# SmartLEDS.net
KiCad netlist of a schematic drawn in Altium Designer
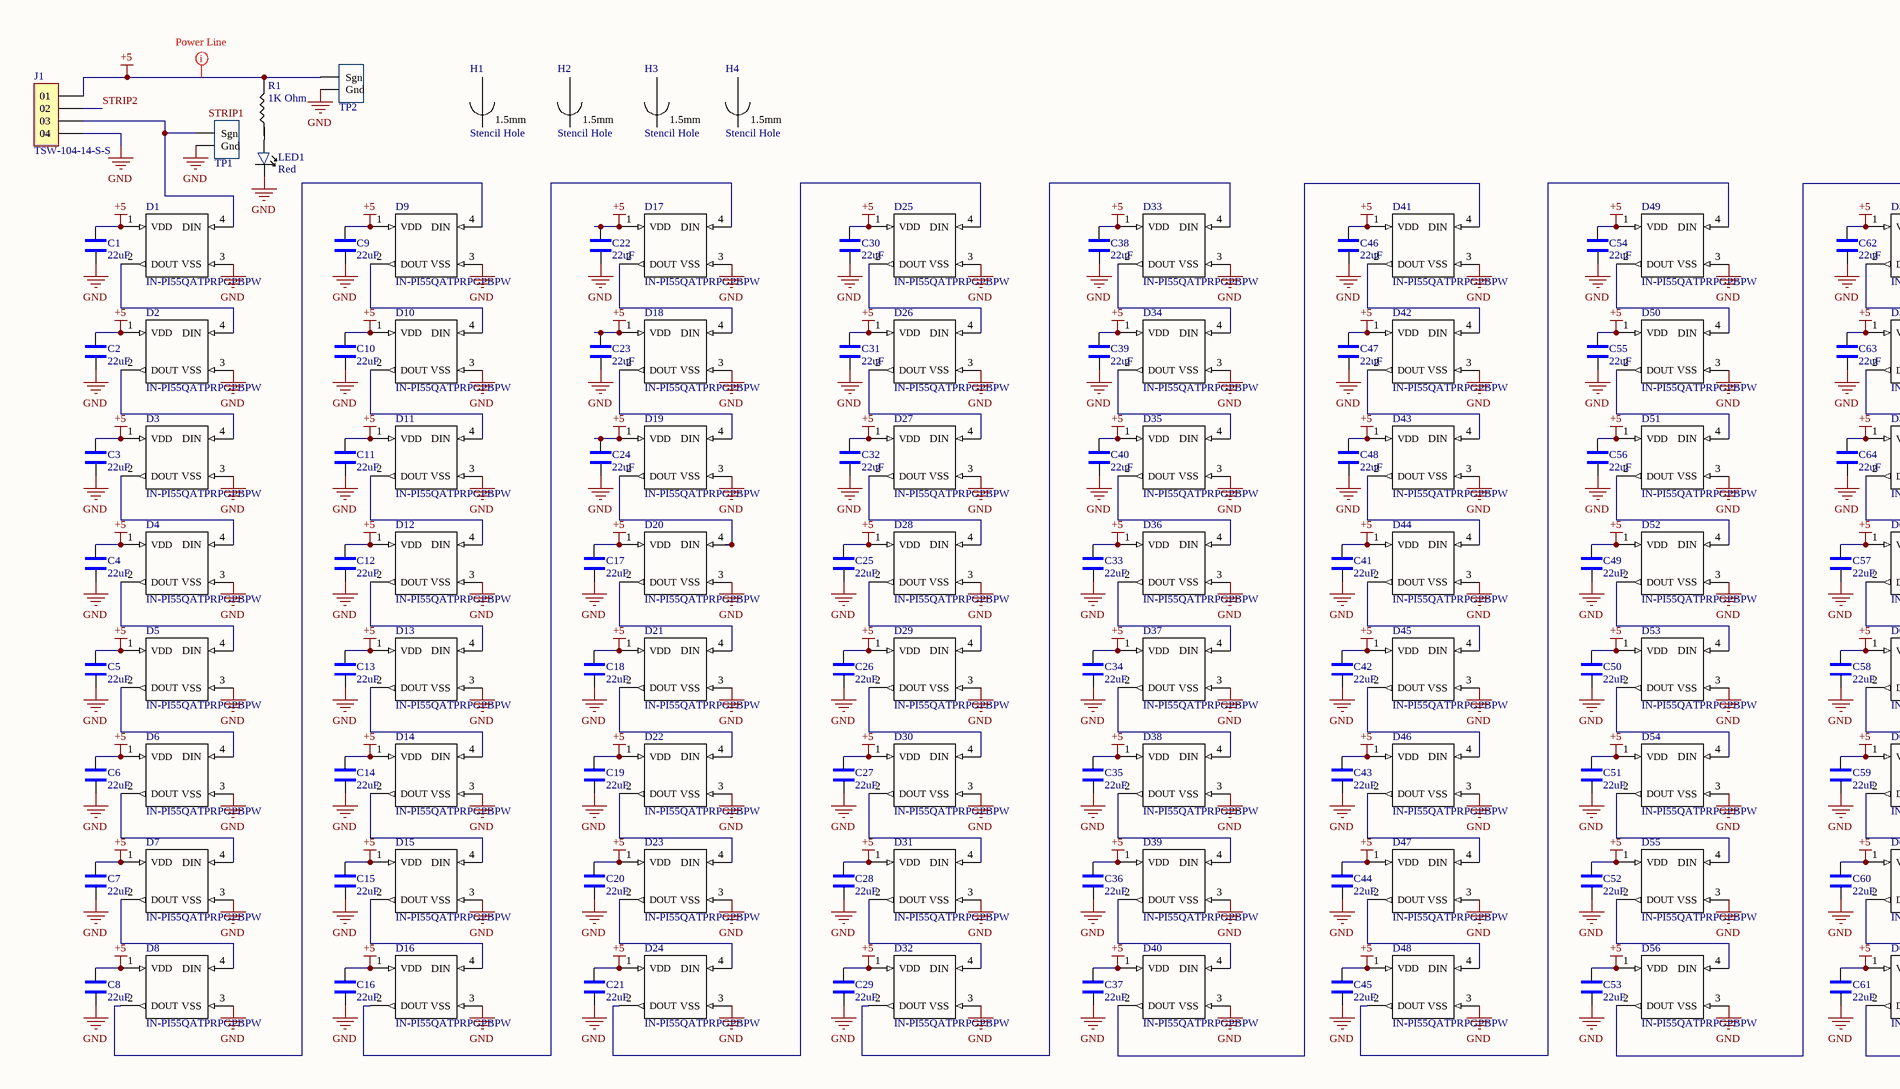
[diagram p0: SmartLEDS.SchDoc, left]
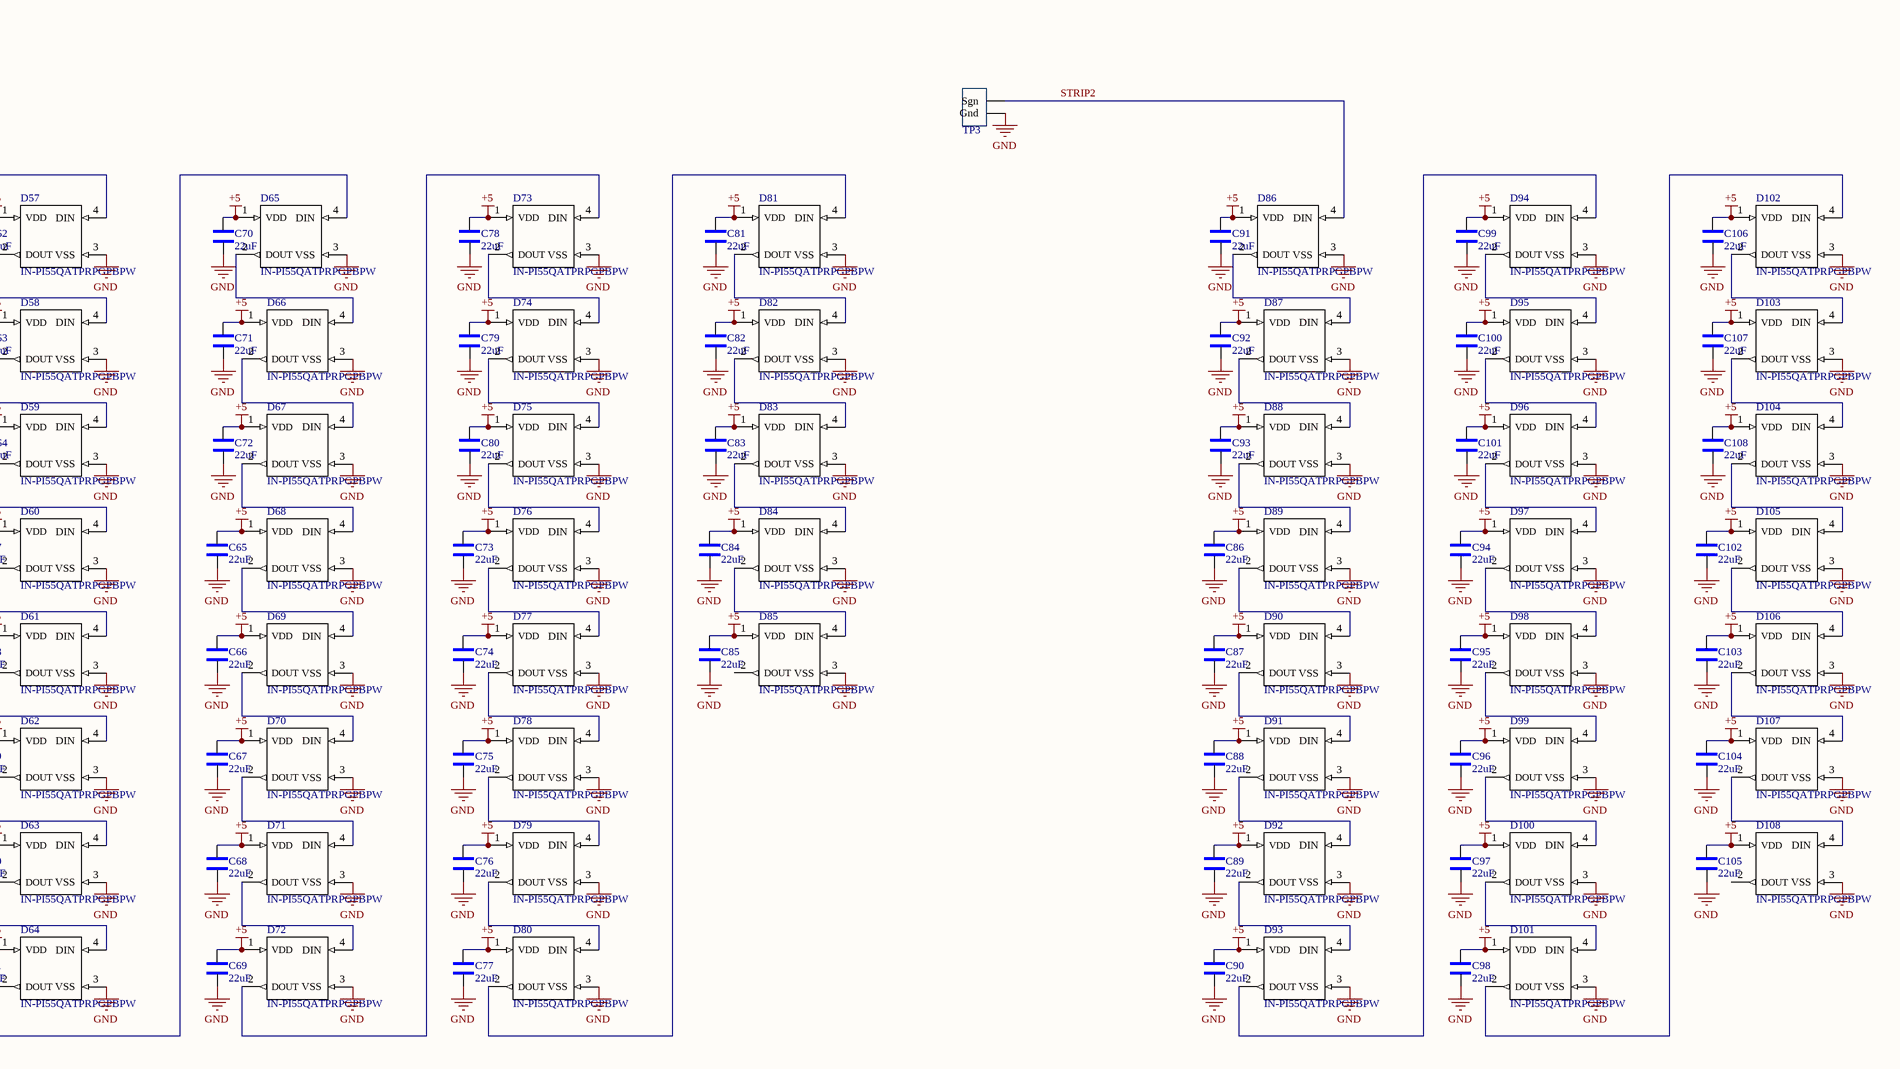
[diagram p1: SmartLEDS.SchDoc, right]

(export (version "E")
  (design (tool "Eeschema 10.0.6"))
  (components
    (comp (ref "C1")
      (value "22uF")
      (footprint "1206_Passive_Capacitor")
      (description "22uF ±10% 25V X5R 1206 Multilayer Ceramic Capacitors MLCC - SMD/SMT RoHS")
      (fields (field (name "MFR PART #") "CL31A226KAHNNNE") (field (name "LCSC PART#") "C12891"))
      (libsource (lib "ECEN5730Lib_2023_05_DS") (part "C_22uF_1206"))
    )
    (comp (ref "C2")
      (value "22uF")
      (footprint "1206_Passive_Capacitor")
      (description "22uF ±10% 25V X5R 1206 Multilayer Ceramic Capacitors MLCC - SMD/SMT RoHS")
      (fields (field (name "MFR PART #") "CL31A226KAHNNNE") (field (name "LCSC PART#") "C12891"))
      (libsource (lib "ECEN5730Lib_2023_05_DS") (part "C_22uF_1206"))
    )
    (comp (ref "C3")
      (value "22uF")
      (footprint "1206_Passive_Capacitor")
      (description "22uF ±10% 25V X5R 1206 Multilayer Ceramic Capacitors MLCC - SMD/SMT RoHS")
      (fields (field (name "MFR PART #") "CL31A226KAHNNNE") (field (name "LCSC PART#") "C12891"))
      (libsource (lib "ECEN5730Lib_2023_05_DS") (part "C_22uF_1206"))
    )
    (comp (ref "C4")
      (value "22uF")
      (footprint "1206_Passive_Capacitor")
      (description "22uF ±10% 25V X5R 1206 Multilayer Ceramic Capacitors MLCC - SMD/SMT RoHS")
      (fields (field (name "MFR PART #") "CL31A226KAHNNNE") (field (name "LCSC PART#") "C12891"))
      (libsource (lib "ECEN5730Lib_2023_05_DS") (part "C_22uF_1206"))
    )
    (comp (ref "C5")
      (value "22uF")
      (footprint "1206_Passive_Capacitor")
      (description "22uF ±10% 25V X5R 1206 Multilayer Ceramic Capacitors MLCC - SMD/SMT RoHS")
      (fields (field (name "MFR PART #") "CL31A226KAHNNNE") (field (name "LCSC PART#") "C12891"))
      (libsource (lib "ECEN5730Lib_2023_05_DS") (part "C_22uF_1206"))
    )
    (comp (ref "C6")
      (value "22uF")
      (footprint "1206_Passive_Capacitor")
      (description "22uF ±10% 25V X5R 1206 Multilayer Ceramic Capacitors MLCC - SMD/SMT RoHS")
      (fields (field (name "MFR PART #") "CL31A226KAHNNNE") (field (name "LCSC PART#") "C12891"))
      (libsource (lib "ECEN5730Lib_2023_05_DS") (part "C_22uF_1206"))
    )
    (comp (ref "C7")
      (value "22uF")
      (footprint "1206_Passive_Capacitor")
      (description "22uF ±10% 25V X5R 1206 Multilayer Ceramic Capacitors MLCC - SMD/SMT RoHS")
      (fields (field (name "MFR PART #") "CL31A226KAHNNNE") (field (name "LCSC PART#") "C12891"))
      (libsource (lib "ECEN5730Lib_2023_05_DS") (part "C_22uF_1206"))
    )
    (comp (ref "C8")
      (value "22uF")
      (footprint "1206_Passive_Capacitor")
      (description "22uF ±10% 25V X5R 1206 Multilayer Ceramic Capacitors MLCC - SMD/SMT RoHS")
      (fields (field (name "MFR PART #") "CL31A226KAHNNNE") (field (name "LCSC PART#") "C12891"))
      (libsource (lib "ECEN5730Lib_2023_05_DS") (part "C_22uF_1206"))
    )
    (comp (ref "C9")
      (value "22uF")
      (footprint "1206_Passive_Capacitor")
      (description "22uF ±10% 25V X5R 1206 Multilayer Ceramic Capacitors MLCC - SMD/SMT RoHS")
      (fields (field (name "MFR PART #") "CL31A226KAHNNNE") (field (name "LCSC PART#") "C12891"))
      (libsource (lib "ECEN5730Lib_2023_05_DS") (part "C_22uF_1206"))
    )
    (comp (ref "C10")
      (value "22uF")
      (footprint "1206_Passive_Capacitor")
      (description "22uF ±10% 25V X5R 1206 Multilayer Ceramic Capacitors MLCC - SMD/SMT RoHS")
      (fields (field (name "MFR PART #") "CL31A226KAHNNNE") (field (name "LCSC PART#") "C12891"))
      (libsource (lib "ECEN5730Lib_2023_05_DS") (part "C_22uF_1206"))
    )
    (comp (ref "C11")
      (value "22uF")
      (footprint "1206_Passive_Capacitor")
      (description "22uF ±10% 25V X5R 1206 Multilayer Ceramic Capacitors MLCC - SMD/SMT RoHS")
      (fields (field (name "MFR PART #") "CL31A226KAHNNNE") (field (name "LCSC PART#") "C12891"))
      (libsource (lib "ECEN5730Lib_2023_05_DS") (part "C_22uF_1206"))
    )
    (comp (ref "C12")
      (value "22uF")
      (footprint "1206_Passive_Capacitor")
      (description "22uF ±10% 25V X5R 1206 Multilayer Ceramic Capacitors MLCC - SMD/SMT RoHS")
      (fields (field (name "MFR PART #") "CL31A226KAHNNNE") (field (name "LCSC PART#") "C12891"))
      (libsource (lib "ECEN5730Lib_2023_05_DS") (part "C_22uF_1206"))
    )
    (comp (ref "C13")
      (value "22uF")
      (footprint "1206_Passive_Capacitor")
      (description "22uF ±10% 25V X5R 1206 Multilayer Ceramic Capacitors MLCC - SMD/SMT RoHS")
      (fields (field (name "MFR PART #") "CL31A226KAHNNNE") (field (name "LCSC PART#") "C12891"))
      (libsource (lib "ECEN5730Lib_2023_05_DS") (part "C_22uF_1206"))
    )
    (comp (ref "C14")
      (value "22uF")
      (footprint "1206_Passive_Capacitor")
      (description "22uF ±10% 25V X5R 1206 Multilayer Ceramic Capacitors MLCC - SMD/SMT RoHS")
      (fields (field (name "MFR PART #") "CL31A226KAHNNNE") (field (name "LCSC PART#") "C12891"))
      (libsource (lib "ECEN5730Lib_2023_05_DS") (part "C_22uF_1206"))
    )
    (comp (ref "C15")
      (value "22uF")
      (footprint "1206_Passive_Capacitor")
      (description "22uF ±10% 25V X5R 1206 Multilayer Ceramic Capacitors MLCC - SMD/SMT RoHS")
      (fields (field (name "MFR PART #") "CL31A226KAHNNNE") (field (name "LCSC PART#") "C12891"))
      (libsource (lib "ECEN5730Lib_2023_05_DS") (part "C_22uF_1206"))
    )
    (comp (ref "C16")
      (value "22uF")
      (footprint "1206_Passive_Capacitor")
      (description "22uF ±10% 25V X5R 1206 Multilayer Ceramic Capacitors MLCC - SMD/SMT RoHS")
      (fields (field (name "MFR PART #") "CL31A226KAHNNNE") (field (name "LCSC PART#") "C12891"))
      (libsource (lib "ECEN5730Lib_2023_05_DS") (part "C_22uF_1206"))
    )
    (comp (ref "C17")
      (value "22uF")
      (footprint "1206_Passive_Capacitor")
      (description "22uF ±10% 25V X5R 1206 Multilayer Ceramic Capacitors MLCC - SMD/SMT RoHS")
      (fields (field (name "MFR PART #") "CL31A226KAHNNNE") (field (name "LCSC PART#") "C12891"))
      (libsource (lib "ECEN5730Lib_2023_05_DS") (part "C_22uF_1206"))
    )
    (comp (ref "C18")
      (value "22uF")
      (footprint "1206_Passive_Capacitor")
      (description "22uF ±10% 25V X5R 1206 Multilayer Ceramic Capacitors MLCC - SMD/SMT RoHS")
      (fields (field (name "MFR PART #") "CL31A226KAHNNNE") (field (name "LCSC PART#") "C12891"))
      (libsource (lib "ECEN5730Lib_2023_05_DS") (part "C_22uF_1206"))
    )
    (comp (ref "C19")
      (value "22uF")
      (footprint "1206_Passive_Capacitor")
      (description "22uF ±10% 25V X5R 1206 Multilayer Ceramic Capacitors MLCC - SMD/SMT RoHS")
      (fields (field (name "MFR PART #") "CL31A226KAHNNNE") (field (name "LCSC PART#") "C12891"))
      (libsource (lib "ECEN5730Lib_2023_05_DS") (part "C_22uF_1206"))
    )
    (comp (ref "C20")
      (value "22uF")
      (footprint "1206_Passive_Capacitor")
      (description "22uF ±10% 25V X5R 1206 Multilayer Ceramic Capacitors MLCC - SMD/SMT RoHS")
      (fields (field (name "MFR PART #") "CL31A226KAHNNNE") (field (name "LCSC PART#") "C12891"))
      (libsource (lib "ECEN5730Lib_2023_05_DS") (part "C_22uF_1206"))
    )
    (comp (ref "C21")
      (value "22uF")
      (footprint "1206_Passive_Capacitor")
      (description "22uF ±10% 25V X5R 1206 Multilayer Ceramic Capacitors MLCC - SMD/SMT RoHS")
      (fields (field (name "MFR PART #") "CL31A226KAHNNNE") (field (name "LCSC PART#") "C12891"))
      (libsource (lib "ECEN5730Lib_2023_05_DS") (part "C_22uF_1206"))
    )
    (comp (ref "C22")
      (value "22uF")
      (footprint "1206_Passive_Capacitor")
      (description "22uF ±10% 25V X5R 1206 Multilayer Ceramic Capacitors MLCC - SMD/SMT RoHS")
      (fields (field (name "MFR PART #") "CL31A226KAHNNNE") (field (name "LCSC PART#") "C12891"))
      (libsource (lib "ECEN5730Lib_2023_05_DS") (part "C_22uF_1206"))
    )
    (comp (ref "C23")
      (value "22uF")
      (footprint "1206_Passive_Capacitor")
      (description "22uF ±10% 25V X5R 1206 Multilayer Ceramic Capacitors MLCC - SMD/SMT RoHS")
      (fields (field (name "MFR PART #") "CL31A226KAHNNNE") (field (name "LCSC PART#") "C12891"))
      (libsource (lib "ECEN5730Lib_2023_05_DS") (part "C_22uF_1206"))
    )
    (comp (ref "C24")
      (value "22uF")
      (footprint "1206_Passive_Capacitor")
      (description "22uF ±10% 25V X5R 1206 Multilayer Ceramic Capacitors MLCC - SMD/SMT RoHS")
      (fields (field (name "MFR PART #") "CL31A226KAHNNNE") (field (name "LCSC PART#") "C12891"))
      (libsource (lib "ECEN5730Lib_2023_05_DS") (part "C_22uF_1206"))
    )
    (comp (ref "C25")
      (value "22uF")
      (footprint "1206_Passive_Capacitor")
      (description "22uF ±10% 25V X5R 1206 Multilayer Ceramic Capacitors MLCC - SMD/SMT RoHS")
      (fields (field (name "MFR PART #") "CL31A226KAHNNNE") (field (name "LCSC PART#") "C12891"))
      (libsource (lib "ECEN5730Lib_2023_05_DS") (part "C_22uF_1206"))
    )
    (comp (ref "C26")
      (value "22uF")
      (footprint "1206_Passive_Capacitor")
      (description "22uF ±10% 25V X5R 1206 Multilayer Ceramic Capacitors MLCC - SMD/SMT RoHS")
      (fields (field (name "MFR PART #") "CL31A226KAHNNNE") (field (name "LCSC PART#") "C12891"))
      (libsource (lib "ECEN5730Lib_2023_05_DS") (part "C_22uF_1206"))
    )
    (comp (ref "C27")
      (value "22uF")
      (footprint "1206_Passive_Capacitor")
      (description "22uF ±10% 25V X5R 1206 Multilayer Ceramic Capacitors MLCC - SMD/SMT RoHS")
      (fields (field (name "MFR PART #") "CL31A226KAHNNNE") (field (name "LCSC PART#") "C12891"))
      (libsource (lib "ECEN5730Lib_2023_05_DS") (part "C_22uF_1206"))
    )
    (comp (ref "C28")
      (value "22uF")
      (footprint "1206_Passive_Capacitor")
      (description "22uF ±10% 25V X5R 1206 Multilayer Ceramic Capacitors MLCC - SMD/SMT RoHS")
      (fields (field (name "MFR PART #") "CL31A226KAHNNNE") (field (name "LCSC PART#") "C12891"))
      (libsource (lib "ECEN5730Lib_2023_05_DS") (part "C_22uF_1206"))
    )
    (comp (ref "C29")
      (value "22uF")
      (footprint "1206_Passive_Capacitor")
      (description "22uF ±10% 25V X5R 1206 Multilayer Ceramic Capacitors MLCC - SMD/SMT RoHS")
      (fields (field (name "MFR PART #") "CL31A226KAHNNNE") (field (name "LCSC PART#") "C12891"))
      (libsource (lib "ECEN5730Lib_2023_05_DS") (part "C_22uF_1206"))
    )
    (comp (ref "C30")
      (value "22uF")
      (footprint "1206_Passive_Capacitor")
      (description "22uF ±10% 25V X5R 1206 Multilayer Ceramic Capacitors MLCC - SMD/SMT RoHS")
      (fields (field (name "MFR PART #") "CL31A226KAHNNNE") (field (name "LCSC PART#") "C12891"))
      (libsource (lib "ECEN5730Lib_2023_05_DS") (part "C_22uF_1206"))
    )
    (comp (ref "C31")
      (value "22uF")
      (footprint "1206_Passive_Capacitor")
      (description "22uF ±10% 25V X5R 1206 Multilayer Ceramic Capacitors MLCC - SMD/SMT RoHS")
      (fields (field (name "MFR PART #") "CL31A226KAHNNNE") (field (name "LCSC PART#") "C12891"))
      (libsource (lib "ECEN5730Lib_2023_05_DS") (part "C_22uF_1206"))
    )
    (comp (ref "C32")
      (value "22uF")
      (footprint "1206_Passive_Capacitor")
      (description "22uF ±10% 25V X5R 1206 Multilayer Ceramic Capacitors MLCC - SMD/SMT RoHS")
      (fields (field (name "MFR PART #") "CL31A226KAHNNNE") (field (name "LCSC PART#") "C12891"))
      (libsource (lib "ECEN5730Lib_2023_05_DS") (part "C_22uF_1206"))
    )
    (comp (ref "C33")
      (value "22uF")
      (footprint "1206_Passive_Capacitor")
      (description "22uF ±10% 25V X5R 1206 Multilayer Ceramic Capacitors MLCC - SMD/SMT RoHS")
      (fields (field (name "MFR PART #") "CL31A226KAHNNNE") (field (name "LCSC PART#") "C12891"))
      (libsource (lib "ECEN5730Lib_2023_05_DS") (part "C_22uF_1206"))
    )
    (comp (ref "C34")
      (value "22uF")
      (footprint "1206_Passive_Capacitor")
      (description "22uF ±10% 25V X5R 1206 Multilayer Ceramic Capacitors MLCC - SMD/SMT RoHS")
      (fields (field (name "MFR PART #") "CL31A226KAHNNNE") (field (name "LCSC PART#") "C12891"))
      (libsource (lib "ECEN5730Lib_2023_05_DS") (part "C_22uF_1206"))
    )
    (comp (ref "C35")
      (value "22uF")
      (footprint "1206_Passive_Capacitor")
      (description "22uF ±10% 25V X5R 1206 Multilayer Ceramic Capacitors MLCC - SMD/SMT RoHS")
      (fields (field (name "MFR PART #") "CL31A226KAHNNNE") (field (name "LCSC PART#") "C12891"))
      (libsource (lib "ECEN5730Lib_2023_05_DS") (part "C_22uF_1206"))
    )
    (comp (ref "C36")
      (value "22uF")
      (footprint "1206_Passive_Capacitor")
      (description "22uF ±10% 25V X5R 1206 Multilayer Ceramic Capacitors MLCC - SMD/SMT RoHS")
      (fields (field (name "MFR PART #") "CL31A226KAHNNNE") (field (name "LCSC PART#") "C12891"))
      (libsource (lib "ECEN5730Lib_2023_05_DS") (part "C_22uF_1206"))
    )
    (comp (ref "C37")
      (value "22uF")
      (footprint "1206_Passive_Capacitor")
      (description "22uF ±10% 25V X5R 1206 Multilayer Ceramic Capacitors MLCC - SMD/SMT RoHS")
      (fields (field (name "MFR PART #") "CL31A226KAHNNNE") (field (name "LCSC PART#") "C12891"))
      (libsource (lib "ECEN5730Lib_2023_05_DS") (part "C_22uF_1206"))
    )
    (comp (ref "C38")
      (value "22uF")
      (footprint "1206_Passive_Capacitor")
      (description "22uF ±10% 25V X5R 1206 Multilayer Ceramic Capacitors MLCC - SMD/SMT RoHS")
      (fields (field (name "MFR PART #") "CL31A226KAHNNNE") (field (name "LCSC PART#") "C12891"))
      (libsource (lib "ECEN5730Lib_2023_05_DS") (part "C_22uF_1206"))
    )
    (comp (ref "C39")
      (value "22uF")
      (footprint "1206_Passive_Capacitor")
      (description "22uF ±10% 25V X5R 1206 Multilayer Ceramic Capacitors MLCC - SMD/SMT RoHS")
      (fields (field (name "MFR PART #") "CL31A226KAHNNNE") (field (name "LCSC PART#") "C12891"))
      (libsource (lib "ECEN5730Lib_2023_05_DS") (part "C_22uF_1206"))
    )
    (comp (ref "C40")
      (value "22uF")
      (footprint "1206_Passive_Capacitor")
      (description "22uF ±10% 25V X5R 1206 Multilayer Ceramic Capacitors MLCC - SMD/SMT RoHS")
      (fields (field (name "MFR PART #") "CL31A226KAHNNNE") (field (name "LCSC PART#") "C12891"))
      (libsource (lib "ECEN5730Lib_2023_05_DS") (part "C_22uF_1206"))
    )
    (comp (ref "C41")
      (value "22uF")
      (footprint "1206_Passive_Capacitor")
      (description "22uF ±10% 25V X5R 1206 Multilayer Ceramic Capacitors MLCC - SMD/SMT RoHS")
      (fields (field (name "MFR PART #") "CL31A226KAHNNNE") (field (name "LCSC PART#") "C12891"))
      (libsource (lib "ECEN5730Lib_2023_05_DS") (part "C_22uF_1206"))
    )
    (comp (ref "C42")
      (value "22uF")
      (footprint "1206_Passive_Capacitor")
      (description "22uF ±10% 25V X5R 1206 Multilayer Ceramic Capacitors MLCC - SMD/SMT RoHS")
      (fields (field (name "MFR PART #") "CL31A226KAHNNNE") (field (name "LCSC PART#") "C12891"))
      (libsource (lib "ECEN5730Lib_2023_05_DS") (part "C_22uF_1206"))
    )
    (comp (ref "C43")
      (value "22uF")
      (footprint "1206_Passive_Capacitor")
      (description "22uF ±10% 25V X5R 1206 Multilayer Ceramic Capacitors MLCC - SMD/SMT RoHS")
      (fields (field (name "MFR PART #") "CL31A226KAHNNNE") (field (name "LCSC PART#") "C12891"))
      (libsource (lib "ECEN5730Lib_2023_05_DS") (part "C_22uF_1206"))
    )
    (comp (ref "C44")
      (value "22uF")
      (footprint "1206_Passive_Capacitor")
      (description "22uF ±10% 25V X5R 1206 Multilayer Ceramic Capacitors MLCC - SMD/SMT RoHS")
      (fields (field (name "MFR PART #") "CL31A226KAHNNNE") (field (name "LCSC PART#") "C12891"))
      (libsource (lib "ECEN5730Lib_2023_05_DS") (part "C_22uF_1206"))
    )
    (comp (ref "C45")
      (value "22uF")
      (footprint "1206_Passive_Capacitor")
      (description "22uF ±10% 25V X5R 1206 Multilayer Ceramic Capacitors MLCC - SMD/SMT RoHS")
      (fields (field (name "MFR PART #") "CL31A226KAHNNNE") (field (name "LCSC PART#") "C12891"))
      (libsource (lib "ECEN5730Lib_2023_05_DS") (part "C_22uF_1206"))
    )
    (comp (ref "C46")
      (value "22uF")
      (footprint "1206_Passive_Capacitor")
      (description "22uF ±10% 25V X5R 1206 Multilayer Ceramic Capacitors MLCC - SMD/SMT RoHS")
      (fields (field (name "MFR PART #") "CL31A226KAHNNNE") (field (name "LCSC PART#") "C12891"))
      (libsource (lib "ECEN5730Lib_2023_05_DS") (part "C_22uF_1206"))
    )
    (comp (ref "C47")
      (value "22uF")
      (footprint "1206_Passive_Capacitor")
      (description "22uF ±10% 25V X5R 1206 Multilayer Ceramic Capacitors MLCC - SMD/SMT RoHS")
      (fields (field (name "MFR PART #") "CL31A226KAHNNNE") (field (name "LCSC PART#") "C12891"))
      (libsource (lib "ECEN5730Lib_2023_05_DS") (part "C_22uF_1206"))
    )
    (comp (ref "C48")
      (value "22uF")
      (footprint "1206_Passive_Capacitor")
      (description "22uF ±10% 25V X5R 1206 Multilayer Ceramic Capacitors MLCC - SMD/SMT RoHS")
      (fields (field (name "MFR PART #") "CL31A226KAHNNNE") (field (name "LCSC PART#") "C12891"))
      (libsource (lib "ECEN5730Lib_2023_05_DS") (part "C_22uF_1206"))
    )
    (comp (ref "C49")
      (value "22uF")
      (footprint "1206_Passive_Capacitor")
      (description "22uF ±10% 25V X5R 1206 Multilayer Ceramic Capacitors MLCC - SMD/SMT RoHS")
      (fields (field (name "MFR PART #") "CL31A226KAHNNNE") (field (name "LCSC PART#") "C12891"))
      (libsource (lib "ECEN5730Lib_2023_05_DS") (part "C_22uF_1206"))
    )
    (comp (ref "C50")
      (value "22uF")
      (footprint "1206_Passive_Capacitor")
      (description "22uF ±10% 25V X5R 1206 Multilayer Ceramic Capacitors MLCC - SMD/SMT RoHS")
      (fields (field (name "MFR PART #") "CL31A226KAHNNNE") (field (name "LCSC PART#") "C12891"))
      (libsource (lib "ECEN5730Lib_2023_05_DS") (part "C_22uF_1206"))
    )
    (comp (ref "C51")
      (value "22uF")
      (footprint "1206_Passive_Capacitor")
      (description "22uF ±10% 25V X5R 1206 Multilayer Ceramic Capacitors MLCC - SMD/SMT RoHS")
      (fields (field (name "MFR PART #") "CL31A226KAHNNNE") (field (name "LCSC PART#") "C12891"))
      (libsource (lib "ECEN5730Lib_2023_05_DS") (part "C_22uF_1206"))
    )
    (comp (ref "C52")
      (value "22uF")
      (footprint "1206_Passive_Capacitor")
      (description "22uF ±10% 25V X5R 1206 Multilayer Ceramic Capacitors MLCC - SMD/SMT RoHS")
      (fields (field (name "MFR PART #") "CL31A226KAHNNNE") (field (name "LCSC PART#") "C12891"))
      (libsource (lib "ECEN5730Lib_2023_05_DS") (part "C_22uF_1206"))
    )
    (comp (ref "C53")
      (value "22uF")
      (footprint "1206_Passive_Capacitor")
      (description "22uF ±10% 25V X5R 1206 Multilayer Ceramic Capacitors MLCC - SMD/SMT RoHS")
      (fields (field (name "MFR PART #") "CL31A226KAHNNNE") (field (name "LCSC PART#") "C12891"))
      (libsource (lib "ECEN5730Lib_2023_05_DS") (part "C_22uF_1206"))
    )
    (comp (ref "C54")
      (value "22uF")
      (footprint "1206_Passive_Capacitor")
      (description "22uF ±10% 25V X5R 1206 Multilayer Ceramic Capacitors MLCC - SMD/SMT RoHS")
      (fields (field (name "MFR PART #") "CL31A226KAHNNNE") (field (name "LCSC PART#") "C12891"))
      (libsource (lib "ECEN5730Lib_2023_05_DS") (part "C_22uF_1206"))
    )
    (comp (ref "C55")
      (value "22uF")
      (footprint "1206_Passive_Capacitor")
      (description "22uF ±10% 25V X5R 1206 Multilayer Ceramic Capacitors MLCC - SMD/SMT RoHS")
      (fields (field (name "MFR PART #") "CL31A226KAHNNNE") (field (name "LCSC PART#") "C12891"))
      (libsource (lib "ECEN5730Lib_2023_05_DS") (part "C_22uF_1206"))
    )
    (comp (ref "C56")
      (value "22uF")
      (footprint "1206_Passive_Capacitor")
      (description "22uF ±10% 25V X5R 1206 Multilayer Ceramic Capacitors MLCC - SMD/SMT RoHS")
      (fields (field (name "MFR PART #") "CL31A226KAHNNNE") (field (name "LCSC PART#") "C12891"))
      (libsource (lib "ECEN5730Lib_2023_05_DS") (part "C_22uF_1206"))
    )
    (comp (ref "C57")
      (value "22uF")
      (footprint "1206_Passive_Capacitor")
      (description "22uF ±10% 25V X5R 1206 Multilayer Ceramic Capacitors MLCC - SMD/SMT RoHS")
      (fields (field (name "MFR PART #") "CL31A226KAHNNNE") (field (name "LCSC PART#") "C12891"))
      (libsource (lib "ECEN5730Lib_2023_05_DS") (part "C_22uF_1206"))
    )
    (comp (ref "C58")
      (value "22uF")
      (footprint "1206_Passive_Capacitor")
      (description "22uF ±10% 25V X5R 1206 Multilayer Ceramic Capacitors MLCC - SMD/SMT RoHS")
      (fields (field (name "MFR PART #") "CL31A226KAHNNNE") (field (name "LCSC PART#") "C12891"))
      (libsource (lib "ECEN5730Lib_2023_05_DS") (part "C_22uF_1206"))
    )
    (comp (ref "C59")
      (value "22uF")
      (footprint "1206_Passive_Capacitor")
      (description "22uF ±10% 25V X5R 1206 Multilayer Ceramic Capacitors MLCC - SMD/SMT RoHS")
      (fields (field (name "MFR PART #") "CL31A226KAHNNNE") (field (name "LCSC PART#") "C12891"))
      (libsource (lib "ECEN5730Lib_2023_05_DS") (part "C_22uF_1206"))
    )
    (comp (ref "C60")
      (value "22uF")
      (footprint "1206_Passive_Capacitor")
      (description "22uF ±10% 25V X5R 1206 Multilayer Ceramic Capacitors MLCC - SMD/SMT RoHS")
      (fields (field (name "MFR PART #") "CL31A226KAHNNNE") (field (name "LCSC PART#") "C12891"))
      (libsource (lib "ECEN5730Lib_2023_05_DS") (part "C_22uF_1206"))
    )
    (comp (ref "C61")
      (value "22uF")
      (footprint "1206_Passive_Capacitor")
      (description "22uF ±10% 25V X5R 1206 Multilayer Ceramic Capacitors MLCC - SMD/SMT RoHS")
      (fields (field (name "MFR PART #") "CL31A226KAHNNNE") (field (name "LCSC PART#") "C12891"))
      (libsource (lib "ECEN5730Lib_2023_05_DS") (part "C_22uF_1206"))
    )
    (comp (ref "C62")
      (value "22uF")
      (footprint "1206_Passive_Capacitor")
      (description "22uF ±10% 25V X5R 1206 Multilayer Ceramic Capacitors MLCC - SMD/SMT RoHS")
      (fields (field (name "MFR PART #") "CL31A226KAHNNNE") (field (name "LCSC PART#") "C12891"))
      (libsource (lib "ECEN5730Lib_2023_05_DS") (part "C_22uF_1206"))
    )
    (comp (ref "C63")
      (value "22uF")
      (footprint "1206_Passive_Capacitor")
      (description "22uF ±10% 25V X5R 1206 Multilayer Ceramic Capacitors MLCC - SMD/SMT RoHS")
      (fields (field (name "MFR PART #") "CL31A226KAHNNNE") (field (name "LCSC PART#") "C12891"))
      (libsource (lib "ECEN5730Lib_2023_05_DS") (part "C_22uF_1206"))
    )
    (comp (ref "C64")
      (value "22uF")
      (footprint "1206_Passive_Capacitor")
      (description "22uF ±10% 25V X5R 1206 Multilayer Ceramic Capacitors MLCC - SMD/SMT RoHS")
      (fields (field (name "MFR PART #") "CL31A226KAHNNNE") (field (name "LCSC PART#") "C12891"))
      (libsource (lib "ECEN5730Lib_2023_05_DS") (part "C_22uF_1206"))
    )
    (comp (ref "C65")
      (value "22uF")
      (footprint "1206_Passive_Capacitor")
      (description "22uF ±10% 25V X5R 1206 Multilayer Ceramic Capacitors MLCC - SMD/SMT RoHS")
      (fields (field (name "MFR PART #") "CL31A226KAHNNNE") (field (name "LCSC PART#") "C12891"))
      (libsource (lib "ECEN5730Lib_2023_05_DS") (part "C_22uF_1206"))
    )
    (comp (ref "C66")
      (value "22uF")
      (footprint "1206_Passive_Capacitor")
      (description "22uF ±10% 25V X5R 1206 Multilayer Ceramic Capacitors MLCC - SMD/SMT RoHS")
      (fields (field (name "MFR PART #") "CL31A226KAHNNNE") (field (name "LCSC PART#") "C12891"))
      (libsource (lib "ECEN5730Lib_2023_05_DS") (part "C_22uF_1206"))
    )
    (comp (ref "C67")
      (value "22uF")
      (footprint "1206_Passive_Capacitor")
      (description "22uF ±10% 25V X5R 1206 Multilayer Ceramic Capacitors MLCC - SMD/SMT RoHS")
      (fields (field (name "MFR PART #") "CL31A226KAHNNNE") (field (name "LCSC PART#") "C12891"))
      (libsource (lib "ECEN5730Lib_2023_05_DS") (part "C_22uF_1206"))
    )
    (comp (ref "C68")
      (value "22uF")
      (footprint "1206_Passive_Capacitor")
      (description "22uF ±10% 25V X5R 1206 Multilayer Ceramic Capacitors MLCC - SMD/SMT RoHS")
      (fields (field (name "MFR PART #") "CL31A226KAHNNNE") (field (name "LCSC PART#") "C12891"))
      (libsource (lib "ECEN5730Lib_2023_05_DS") (part "C_22uF_1206"))
    )
    (comp (ref "C69")
      (value "22uF")
      (footprint "1206_Passive_Capacitor")
      (description "22uF ±10% 25V X5R 1206 Multilayer Ceramic Capacitors MLCC - SMD/SMT RoHS")
      (fields (field (name "MFR PART #") "CL31A226KAHNNNE") (field (name "LCSC PART#") "C12891"))
      (libsource (lib "ECEN5730Lib_2023_05_DS") (part "C_22uF_1206"))
    )
    (comp (ref "C70")
      (value "22uF")
      (footprint "1206_Passive_Capacitor")
      (description "22uF ±10% 25V X5R 1206 Multilayer Ceramic Capacitors MLCC - SMD/SMT RoHS")
      (fields (field (name "MFR PART #") "CL31A226KAHNNNE") (field (name "LCSC PART#") "C12891"))
      (libsource (lib "ECEN5730Lib_2023_05_DS") (part "C_22uF_1206"))
    )
    (comp (ref "C71")
      (value "22uF")
      (footprint "1206_Passive_Capacitor")
      (description "22uF ±10% 25V X5R 1206 Multilayer Ceramic Capacitors MLCC - SMD/SMT RoHS")
      (fields (field (name "MFR PART #") "CL31A226KAHNNNE") (field (name "LCSC PART#") "C12891"))
      (libsource (lib "ECEN5730Lib_2023_05_DS") (part "C_22uF_1206"))
    )
    (comp (ref "C72")
      (value "22uF")
      (footprint "1206_Passive_Capacitor")
      (description "22uF ±10% 25V X5R 1206 Multilayer Ceramic Capacitors MLCC - SMD/SMT RoHS")
      (fields (field (name "MFR PART #") "CL31A226KAHNNNE") (field (name "LCSC PART#") "C12891"))
      (libsource (lib "ECEN5730Lib_2023_05_DS") (part "C_22uF_1206"))
    )
    (comp (ref "C73")
      (value "22uF")
      (footprint "1206_Passive_Capacitor")
      (description "22uF ±10% 25V X5R 1206 Multilayer Ceramic Capacitors MLCC - SMD/SMT RoHS")
      (fields (field (name "MFR PART #") "CL31A226KAHNNNE") (field (name "LCSC PART#") "C12891"))
      (libsource (lib "ECEN5730Lib_2023_05_DS") (part "C_22uF_1206"))
    )
    (comp (ref "C74")
      (value "22uF")
      (footprint "1206_Passive_Capacitor")
      (description "22uF ±10% 25V X5R 1206 Multilayer Ceramic Capacitors MLCC - SMD/SMT RoHS")
      (fields (field (name "MFR PART #") "CL31A226KAHNNNE") (field (name "LCSC PART#") "C12891"))
      (libsource (lib "ECEN5730Lib_2023_05_DS") (part "C_22uF_1206"))
    )
    (comp (ref "C75")
      (value "22uF")
      (footprint "1206_Passive_Capacitor")
      (description "22uF ±10% 25V X5R 1206 Multilayer Ceramic Capacitors MLCC - SMD/SMT RoHS")
      (fields (field (name "MFR PART #") "CL31A226KAHNNNE") (field (name "LCSC PART#") "C12891"))
      (libsource (lib "ECEN5730Lib_2023_05_DS") (part "C_22uF_1206"))
    )
    (comp (ref "C76")
      (value "22uF")
      (footprint "1206_Passive_Capacitor")
      (description "22uF ±10% 25V X5R 1206 Multilayer Ceramic Capacitors MLCC - SMD/SMT RoHS")
      (fields (field (name "MFR PART #") "CL31A226KAHNNNE") (field (name "LCSC PART#") "C12891"))
      (libsource (lib "ECEN5730Lib_2023_05_DS") (part "C_22uF_1206"))
    )
    (comp (ref "C77")
      (value "22uF")
      (footprint "1206_Passive_Capacitor")
      (description "22uF ±10% 25V X5R 1206 Multilayer Ceramic Capacitors MLCC - SMD/SMT RoHS")
      (fields (field (name "MFR PART #") "CL31A226KAHNNNE") (field (name "LCSC PART#") "C12891"))
      (libsource (lib "ECEN5730Lib_2023_05_DS") (part "C_22uF_1206"))
    )
    (comp (ref "C78")
      (value "22uF")
      (footprint "1206_Passive_Capacitor")
      (description "22uF ±10% 25V X5R 1206 Multilayer Ceramic Capacitors MLCC - SMD/SMT RoHS")
      (fields (field (name "MFR PART #") "CL31A226KAHNNNE") (field (name "LCSC PART#") "C12891"))
      (libsource (lib "ECEN5730Lib_2023_05_DS") (part "C_22uF_1206"))
    )
    (comp (ref "C79")
      (value "22uF")
      (footprint "1206_Passive_Capacitor")
      (description "22uF ±10% 25V X5R 1206 Multilayer Ceramic Capacitors MLCC - SMD/SMT RoHS")
      (fields (field (name "MFR PART #") "CL31A226KAHNNNE") (field (name "LCSC PART#") "C12891"))
      (libsource (lib "ECEN5730Lib_2023_05_DS") (part "C_22uF_1206"))
    )
    (comp (ref "C80")
      (value "22uF")
      (footprint "1206_Passive_Capacitor")
      (description "22uF ±10% 25V X5R 1206 Multilayer Ceramic Capacitors MLCC - SMD/SMT RoHS")
      (fields (field (name "MFR PART #") "CL31A226KAHNNNE") (field (name "LCSC PART#") "C12891"))
      (libsource (lib "ECEN5730Lib_2023_05_DS") (part "C_22uF_1206"))
    )
    (comp (ref "C81")
      (value "22uF")
      (footprint "1206_Passive_Capacitor")
      (description "22uF ±10% 25V X5R 1206 Multilayer Ceramic Capacitors MLCC - SMD/SMT RoHS")
      (fields (field (name "MFR PART #") "CL31A226KAHNNNE") (field (name "LCSC PART#") "C12891"))
      (libsource (lib "ECEN5730Lib_2023_05_DS") (part "C_22uF_1206"))
    )
    (comp (ref "C82")
      (value "22uF")
      (footprint "1206_Passive_Capacitor")
      (description "22uF ±10% 25V X5R 1206 Multilayer Ceramic Capacitors MLCC - SMD/SMT RoHS")
      (fields (field (name "MFR PART #") "CL31A226KAHNNNE") (field (name "LCSC PART#") "C12891"))
      (libsource (lib "ECEN5730Lib_2023_05_DS") (part "C_22uF_1206"))
    )
    (comp (ref "C83")
      (value "22uF")
      (footprint "1206_Passive_Capacitor")
      (description "22uF ±10% 25V X5R 1206 Multilayer Ceramic Capacitors MLCC - SMD/SMT RoHS")
      (fields (field (name "MFR PART #") "CL31A226KAHNNNE") (field (name "LCSC PART#") "C12891"))
      (libsource (lib "ECEN5730Lib_2023_05_DS") (part "C_22uF_1206"))
    )
    (comp (ref "C84")
      (value "22uF")
      (footprint "1206_Passive_Capacitor")
      (description "22uF ±10% 25V X5R 1206 Multilayer Ceramic Capacitors MLCC - SMD/SMT RoHS")
      (fields (field (name "MFR PART #") "CL31A226KAHNNNE") (field (name "LCSC PART#") "C12891"))
      (libsource (lib "ECEN5730Lib_2023_05_DS") (part "C_22uF_1206"))
    )
    (comp (ref "C85")
      (value "22uF")
      (footprint "1206_Passive_Capacitor")
      (description "22uF ±10% 25V X5R 1206 Multilayer Ceramic Capacitors MLCC - SMD/SMT RoHS")
      (fields (field (name "MFR PART #") "CL31A226KAHNNNE") (field (name "LCSC PART#") "C12891"))
      (libsource (lib "ECEN5730Lib_2023_05_DS") (part "C_22uF_1206"))
    )
    (comp (ref "C86")
      (value "22uF")
      (footprint "1206_Passive_Capacitor")
      (description "22uF ±10% 25V X5R 1206 Multilayer Ceramic Capacitors MLCC - SMD/SMT RoHS")
      (fields (field (name "MFR PART #") "CL31A226KAHNNNE") (field (name "LCSC PART#") "C12891"))
      (libsource (lib "ECEN5730Lib_2023_05_DS") (part "C_22uF_1206"))
    )
    (comp (ref "C87")
      (value "22uF")
      (footprint "1206_Passive_Capacitor")
      (description "22uF ±10% 25V X5R 1206 Multilayer Ceramic Capacitors MLCC - SMD/SMT RoHS")
      (fields (field (name "MFR PART #") "CL31A226KAHNNNE") (field (name "LCSC PART#") "C12891"))
      (libsource (lib "ECEN5730Lib_2023_05_DS") (part "C_22uF_1206"))
    )
    (comp (ref "C88")
      (value "22uF")
      (footprint "1206_Passive_Capacitor")
      (description "22uF ±10% 25V X5R 1206 Multilayer Ceramic Capacitors MLCC - SMD/SMT RoHS")
      (fields (field (name "MFR PART #") "CL31A226KAHNNNE") (field (name "LCSC PART#") "C12891"))
      (libsource (lib "ECEN5730Lib_2023_05_DS") (part "C_22uF_1206"))
    )
    (comp (ref "C89")
      (value "22uF")
      (footprint "1206_Passive_Capacitor")
      (description "22uF ±10% 25V X5R 1206 Multilayer Ceramic Capacitors MLCC - SMD/SMT RoHS")
      (fields (field (name "MFR PART #") "CL31A226KAHNNNE") (field (name "LCSC PART#") "C12891"))
      (libsource (lib "ECEN5730Lib_2023_05_DS") (part "C_22uF_1206"))
    )
    (comp (ref "C90")
      (value "22uF")
      (footprint "1206_Passive_Capacitor")
      (description "22uF ±10% 25V X5R 1206 Multilayer Ceramic Capacitors MLCC - SMD/SMT RoHS")
      (fields (field (name "MFR PART #") "CL31A226KAHNNNE") (field (name "LCSC PART#") "C12891"))
      (libsource (lib "ECEN5730Lib_2023_05_DS") (part "C_22uF_1206"))
    )
    (comp (ref "C91")
      (value "22uF")
      (footprint "1206_Passive_Capacitor")
      (description "22uF ±10% 25V X5R 1206 Multilayer Ceramic Capacitors MLCC - SMD/SMT RoHS")
      (fields (field (name "MFR PART #") "CL31A226KAHNNNE") (field (name "LCSC PART#") "C12891"))
      (libsource (lib "ECEN5730Lib_2023_05_DS") (part "C_22uF_1206"))
    )
    (comp (ref "C92")
      (value "22uF")
      (footprint "1206_Passive_Capacitor")
      (description "22uF ±10% 25V X5R 1206 Multilayer Ceramic Capacitors MLCC - SMD/SMT RoHS")
      (fields (field (name "MFR PART #") "CL31A226KAHNNNE") (field (name "LCSC PART#") "C12891"))
      (libsource (lib "ECEN5730Lib_2023_05_DS") (part "C_22uF_1206"))
    )
    (comp (ref "C93")
      (value "22uF")
      (footprint "1206_Passive_Capacitor")
      (description "22uF ±10% 25V X5R 1206 Multilayer Ceramic Capacitors MLCC - SMD/SMT RoHS")
      (fields (field (name "MFR PART #") "CL31A226KAHNNNE") (field (name "LCSC PART#") "C12891"))
      (libsource (lib "ECEN5730Lib_2023_05_DS") (part "C_22uF_1206"))
    )
    (comp (ref "C94")
      (value "22uF")
      (footprint "1206_Passive_Capacitor")
      (description "22uF ±10% 25V X5R 1206 Multilayer Ceramic Capacitors MLCC - SMD/SMT RoHS")
      (fields (field (name "MFR PART #") "CL31A226KAHNNNE") (field (name "LCSC PART#") "C12891"))
      (libsource (lib "ECEN5730Lib_2023_05_DS") (part "C_22uF_1206"))
    )
    (comp (ref "C95")
      (value "22uF")
      (footprint "1206_Passive_Capacitor")
      (description "22uF ±10% 25V X5R 1206 Multilayer Ceramic Capacitors MLCC - SMD/SMT RoHS")
      (fields (field (name "MFR PART #") "CL31A226KAHNNNE") (field (name "LCSC PART#") "C12891"))
      (libsource (lib "ECEN5730Lib_2023_05_DS") (part "C_22uF_1206"))
    )
    (comp (ref "C96")
      (value "22uF")
      (footprint "1206_Passive_Capacitor")
      (description "22uF ±10% 25V X5R 1206 Multilayer Ceramic Capacitors MLCC - SMD/SMT RoHS")
      (fields (field (name "MFR PART #") "CL31A226KAHNNNE") (field (name "LCSC PART#") "C12891"))
      (libsource (lib "ECEN5730Lib_2023_05_DS") (part "C_22uF_1206"))
    )
    (comp (ref "C97")
      (value "22uF")
      (footprint "1206_Passive_Capacitor")
      (description "22uF ±10% 25V X5R 1206 Multilayer Ceramic Capacitors MLCC - SMD/SMT RoHS")
      (fields (field (name "MFR PART #") "CL31A226KAHNNNE") (field (name "LCSC PART#") "C12891"))
      (libsource (lib "ECEN5730Lib_2023_05_DS") (part "C_22uF_1206"))
    )
    (comp (ref "C98")
      (value "22uF")
      (footprint "1206_Passive_Capacitor")
      (description "22uF ±10% 25V X5R 1206 Multilayer Ceramic Capacitors MLCC - SMD/SMT RoHS")
      (fields (field (name "MFR PART #") "CL31A226KAHNNNE") (field (name "LCSC PART#") "C12891"))
      (libsource (lib "ECEN5730Lib_2023_05_DS") (part "C_22uF_1206"))
    )
    (comp (ref "C99")
      (value "22uF")
      (footprint "1206_Passive_Capacitor")
      (description "22uF ±10% 25V X5R 1206 Multilayer Ceramic Capacitors MLCC - SMD/SMT RoHS")
      (fields (field (name "MFR PART #") "CL31A226KAHNNNE") (field (name "LCSC PART#") "C12891"))
      (libsource (lib "ECEN5730Lib_2023_05_DS") (part "C_22uF_1206"))
    )
    (comp (ref "C100")
      (value "22uF")
      (footprint "1206_Passive_Capacitor")
      (description "22uF ±10% 25V X5R 1206 Multilayer Ceramic Capacitors MLCC - SMD/SMT RoHS")
      (fields (field (name "MFR PART #") "CL31A226KAHNNNE") (field (name "LCSC PART#") "C12891"))
      (libsource (lib "ECEN5730Lib_2023_05_DS") (part "C_22uF_1206"))
    )
    (comp (ref "C101")
      (value "22uF")
      (footprint "1206_Passive_Capacitor")
      (description "22uF ±10% 25V X5R 1206 Multilayer Ceramic Capacitors MLCC - SMD/SMT RoHS")
      (fields (field (name "MFR PART #") "CL31A226KAHNNNE") (field (name "LCSC PART#") "C12891"))
      (libsource (lib "ECEN5730Lib_2023_05_DS") (part "C_22uF_1206"))
    )
    (comp (ref "C102")
      (value "22uF")
      (footprint "1206_Passive_Capacitor")
      (description "22uF ±10% 25V X5R 1206 Multilayer Ceramic Capacitors MLCC - SMD/SMT RoHS")
      (fields (field (name "MFR PART #") "CL31A226KAHNNNE") (field (name "LCSC PART#") "C12891"))
      (libsource (lib "ECEN5730Lib_2023_05_DS") (part "C_22uF_1206"))
    )
    (comp (ref "C103")
      (value "22uF")
      (footprint "1206_Passive_Capacitor")
      (description "22uF ±10% 25V X5R 1206 Multilayer Ceramic Capacitors MLCC - SMD/SMT RoHS")
      (fields (field (name "MFR PART #") "CL31A226KAHNNNE") (field (name "LCSC PART#") "C12891"))
      (libsource (lib "ECEN5730Lib_2023_05_DS") (part "C_22uF_1206"))
    )
    (comp (ref "C104")
      (value "22uF")
      (footprint "1206_Passive_Capacitor")
      (description "22uF ±10% 25V X5R 1206 Multilayer Ceramic Capacitors MLCC - SMD/SMT RoHS")
      (fields (field (name "MFR PART #") "CL31A226KAHNNNE") (field (name "LCSC PART#") "C12891"))
      (libsource (lib "ECEN5730Lib_2023_05_DS") (part "C_22uF_1206"))
    )
    (comp (ref "C105")
      (value "22uF")
      (footprint "1206_Passive_Capacitor")
      (description "22uF ±10% 25V X5R 1206 Multilayer Ceramic Capacitors MLCC - SMD/SMT RoHS")
      (fields (field (name "MFR PART #") "CL31A226KAHNNNE") (field (name "LCSC PART#") "C12891"))
      (libsource (lib "ECEN5730Lib_2023_05_DS") (part "C_22uF_1206"))
    )
    (comp (ref "C106")
      (value "22uF")
      (footprint "1206_Passive_Capacitor")
      (description "22uF ±10% 25V X5R 1206 Multilayer Ceramic Capacitors MLCC - SMD/SMT RoHS")
      (fields (field (name "MFR PART #") "CL31A226KAHNNNE") (field (name "LCSC PART#") "C12891"))
      (libsource (lib "ECEN5730Lib_2023_05_DS") (part "C_22uF_1206"))
    )
    (comp (ref "C107")
      (value "22uF")
      (footprint "1206_Passive_Capacitor")
      (description "22uF ±10% 25V X5R 1206 Multilayer Ceramic Capacitors MLCC - SMD/SMT RoHS")
      (fields (field (name "MFR PART #") "CL31A226KAHNNNE") (field (name "LCSC PART#") "C12891"))
      (libsource (lib "ECEN5730Lib_2023_05_DS") (part "C_22uF_1206"))
    )
    (comp (ref "C108")
      (value "22uF")
      (footprint "1206_Passive_Capacitor")
      (description "22uF ±10% 25V X5R 1206 Multilayer Ceramic Capacitors MLCC - SMD/SMT RoHS")
      (fields (field (name "MFR PART #") "CL31A226KAHNNNE") (field (name "LCSC PART#") "C12891"))
      (libsource (lib "ECEN5730Lib_2023_05_DS") (part "C_22uF_1206"))
    )
    (comp (ref "D1")
      (value "IN-PI55QATPRPGPBPW")
      (footprint "SERIAL_LED - duplicate")
      (fields
        (field (name "LCSC PART#") "C2843785")
        (field (name "MFR PART #") "XL-5050RGBC-WS2812B")
        (field (name "MANUFACTURER") "XINGLIGHT")
      )
      (libsource (lib "ECEN5730Lib_2023_05_DS") (part "LED_Smart"))
    )
    (comp (ref "D2")
      (value "IN-PI55QATPRPGPBPW")
      (footprint "SERIAL_LED - duplicate")
      (fields
        (field (name "LCSC PART#") "C2843785")
        (field (name "MFR PART #") "XL-5050RGBC-WS2812B")
        (field (name "MANUFACTURER") "XINGLIGHT")
      )
      (libsource (lib "ECEN5730Lib_2023_05_DS") (part "LED_Smart"))
    )
    (comp (ref "D3")
      (value "IN-PI55QATPRPGPBPW")
      (footprint "SERIAL_LED - duplicate")
      (fields
        (field (name "LCSC PART#") "C2843785")
        (field (name "MFR PART #") "XL-5050RGBC-WS2812B")
        (field (name "MANUFACTURER") "XINGLIGHT")
      )
      (libsource (lib "ECEN5730Lib_2023_05_DS") (part "LED_Smart"))
    )
    (comp (ref "D4")
      (value "IN-PI55QATPRPGPBPW")
      (footprint "SERIAL_LED - duplicate")
      (fields
        (field (name "LCSC PART#") "C2843785")
        (field (name "MFR PART #") "XL-5050RGBC-WS2812B")
        (field (name "MANUFACTURER") "XINGLIGHT")
      )
      (libsource (lib "ECEN5730Lib_2023_05_DS") (part "LED_Smart"))
    )
    (comp (ref "D5")
      (value "IN-PI55QATPRPGPBPW")
      (footprint "SERIAL_LED - duplicate")
      (fields
        (field (name "LCSC PART#") "C2843785")
        (field (name "MFR PART #") "XL-5050RGBC-WS2812B")
        (field (name "MANUFACTURER") "XINGLIGHT")
      )
      (libsource (lib "ECEN5730Lib_2023_05_DS") (part "LED_Smart"))
    )
    (comp (ref "D6")
      (value "IN-PI55QATPRPGPBPW")
      (footprint "SERIAL_LED - duplicate")
      (fields
        (field (name "LCSC PART#") "C2843785")
        (field (name "MFR PART #") "XL-5050RGBC-WS2812B")
        (field (name "MANUFACTURER") "XINGLIGHT")
      )
      (libsource (lib "ECEN5730Lib_2023_05_DS") (part "LED_Smart"))
    )
    (comp (ref "D7")
      (value "IN-PI55QATPRPGPBPW")
      (footprint "SERIAL_LED - duplicate")
      (fields
        (field (name "LCSC PART#") "C2843785")
        (field (name "MFR PART #") "XL-5050RGBC-WS2812B")
        (field (name "MANUFACTURER") "XINGLIGHT")
      )
      (libsource (lib "ECEN5730Lib_2023_05_DS") (part "LED_Smart"))
    )
    (comp (ref "D8")
      (value "IN-PI55QATPRPGPBPW")
      (footprint "SERIAL_LED - duplicate")
      (fields
        (field (name "LCSC PART#") "C2843785")
        (field (name "MFR PART #") "XL-5050RGBC-WS2812B")
        (field (name "MANUFACTURER") "XINGLIGHT")
      )
      (libsource (lib "ECEN5730Lib_2023_05_DS") (part "LED_Smart"))
    )
    (comp (ref "D9")
      (value "IN-PI55QATPRPGPBPW")
      (footprint "SERIAL_LED - duplicate")
      (fields
        (field (name "LCSC PART#") "C2843785")
        (field (name "MFR PART #") "XL-5050RGBC-WS2812B")
        (field (name "MANUFACTURER") "XINGLIGHT")
      )
      (libsource (lib "ECEN5730Lib_2023_05_DS") (part "LED_Smart"))
    )
    (comp (ref "D10")
      (value "IN-PI55QATPRPGPBPW")
      (footprint "SERIAL_LED - duplicate")
      (fields
        (field (name "LCSC PART#") "C2843785")
        (field (name "MFR PART #") "XL-5050RGBC-WS2812B")
        (field (name "MANUFACTURER") "XINGLIGHT")
      )
      (libsource (lib "ECEN5730Lib_2023_05_DS") (part "LED_Smart"))
    )
    (comp (ref "D11")
      (value "IN-PI55QATPRPGPBPW")
      (footprint "SERIAL_LED - duplicate")
      (fields
        (field (name "LCSC PART#") "C2843785")
        (field (name "MFR PART #") "XL-5050RGBC-WS2812B")
        (field (name "MANUFACTURER") "XINGLIGHT")
      )
      (libsource (lib "ECEN5730Lib_2023_05_DS") (part "LED_Smart"))
    )
    (comp (ref "D12")
      (value "IN-PI55QATPRPGPBPW")
      (footprint "SERIAL_LED - duplicate")
      (fields
        (field (name "LCSC PART#") "C2843785")
        (field (name "MFR PART #") "XL-5050RGBC-WS2812B")
        (field (name "MANUFACTURER") "XINGLIGHT")
      )
      (libsource (lib "ECEN5730Lib_2023_05_DS") (part "LED_Smart"))
    )
    (comp (ref "D13")
      (value "IN-PI55QATPRPGPBPW")
      (footprint "SERIAL_LED - duplicate")
      (fields
        (field (name "LCSC PART#") "C2843785")
        (field (name "MFR PART #") "XL-5050RGBC-WS2812B")
        (field (name "MANUFACTURER") "XINGLIGHT")
      )
      (libsource (lib "ECEN5730Lib_2023_05_DS") (part "LED_Smart"))
    )
    (comp (ref "D14")
      (value "IN-PI55QATPRPGPBPW")
      (footprint "SERIAL_LED - duplicate")
      (fields
        (field (name "LCSC PART#") "C2843785")
        (field (name "MFR PART #") "XL-5050RGBC-WS2812B")
        (field (name "MANUFACTURER") "XINGLIGHT")
      )
      (libsource (lib "ECEN5730Lib_2023_05_DS") (part "LED_Smart"))
    )
    (comp (ref "D15")
      (value "IN-PI55QATPRPGPBPW")
      (footprint "SERIAL_LED - duplicate")
      (fields
        (field (name "LCSC PART#") "C2843785")
        (field (name "MFR PART #") "XL-5050RGBC-WS2812B")
        (field (name "MANUFACTURER") "XINGLIGHT")
      )
      (libsource (lib "ECEN5730Lib_2023_05_DS") (part "LED_Smart"))
    )
    (comp (ref "D16")
      (value "IN-PI55QATPRPGPBPW")
      (footprint "SERIAL_LED - duplicate")
      (fields
        (field (name "LCSC PART#") "C2843785")
        (field (name "MFR PART #") "XL-5050RGBC-WS2812B")
        (field (name "MANUFACTURER") "XINGLIGHT")
      )
      (libsource (lib "ECEN5730Lib_2023_05_DS") (part "LED_Smart"))
    )
    (comp (ref "D17")
      (value "IN-PI55QATPRPGPBPW")
      (footprint "SERIAL_LED - duplicate")
      (fields
        (field (name "LCSC PART#") "C2843785")
        (field (name "MFR PART #") "XL-5050RGBC-WS2812B")
        (field (name "MANUFACTURER") "XINGLIGHT")
      )
      (libsource (lib "ECEN5730Lib_2023_05_DS") (part "LED_Smart"))
    )
    (comp (ref "D18")
      (value "IN-PI55QATPRPGPBPW")
      (footprint "SERIAL_LED - duplicate")
      (fields
        (field (name "LCSC PART#") "C2843785")
        (field (name "MFR PART #") "XL-5050RGBC-WS2812B")
        (field (name "MANUFACTURER") "XINGLIGHT")
      )
      (libsource (lib "ECEN5730Lib_2023_05_DS") (part "LED_Smart"))
    )
    (comp (ref "D19")
      (value "IN-PI55QATPRPGPBPW")
      (footprint "SERIAL_LED - duplicate")
      (fields
        (field (name "LCSC PART#") "C2843785")
        (field (name "MFR PART #") "XL-5050RGBC-WS2812B")
        (field (name "MANUFACTURER") "XINGLIGHT")
      )
      (libsource (lib "ECEN5730Lib_2023_05_DS") (part "LED_Smart"))
    )
    (comp (ref "D20")
      (value "IN-PI55QATPRPGPBPW")
      (footprint "SERIAL_LED - duplicate")
      (fields
        (field (name "LCSC PART#") "C2843785")
        (field (name "MFR PART #") "XL-5050RGBC-WS2812B")
        (field (name "MANUFACTURER") "XINGLIGHT")
      )
      (libsource (lib "ECEN5730Lib_2023_05_DS") (part "LED_Smart"))
    )
    (comp (ref "D21")
      (value "IN-PI55QATPRPGPBPW")
      (footprint "SERIAL_LED - duplicate")
      (fields
        (field (name "LCSC PART#") "C2843785")
        (field (name "MFR PART #") "XL-5050RGBC-WS2812B")
        (field (name "MANUFACTURER") "XINGLIGHT")
      )
      (libsource (lib "ECEN5730Lib_2023_05_DS") (part "LED_Smart"))
    )
    (comp (ref "D22")
      (value "IN-PI55QATPRPGPBPW")
      (footprint "SERIAL_LED - duplicate")
      (fields
        (field (name "LCSC PART#") "C2843785")
        (field (name "MFR PART #") "XL-5050RGBC-WS2812B")
        (field (name "MANUFACTURER") "XINGLIGHT")
      )
      (libsource (lib "ECEN5730Lib_2023_05_DS") (part "LED_Smart"))
    )
    (comp (ref "D23")
      (value "IN-PI55QATPRPGPBPW")
      (footprint "SERIAL_LED - duplicate")
      (fields
        (field (name "LCSC PART#") "C2843785")
        (field (name "MFR PART #") "XL-5050RGBC-WS2812B")
        (field (name "MANUFACTURER") "XINGLIGHT")
      )
      (libsource (lib "ECEN5730Lib_2023_05_DS") (part "LED_Smart"))
    )
    (comp (ref "D24")
      (value "IN-PI55QATPRPGPBPW")
      (footprint "SERIAL_LED - duplicate")
      (fields
        (field (name "LCSC PART#") "C2843785")
        (field (name "MFR PART #") "XL-5050RGBC-WS2812B")
        (field (name "MANUFACTURER") "XINGLIGHT")
      )
      (libsource (lib "ECEN5730Lib_2023_05_DS") (part "LED_Smart"))
    )
    (comp (ref "D25")
      (value "IN-PI55QATPRPGPBPW")
      (footprint "SERIAL_LED - duplicate")
      (fields
        (field (name "LCSC PART#") "C2843785")
        (field (name "MFR PART #") "XL-5050RGBC-WS2812B")
        (field (name "MANUFACTURER") "XINGLIGHT")
      )
      (libsource (lib "ECEN5730Lib_2023_05_DS") (part "LED_Smart"))
    )
    (comp (ref "D26")
      (value "IN-PI55QATPRPGPBPW")
      (footprint "SERIAL_LED - duplicate")
      (fields
        (field (name "LCSC PART#") "C2843785")
        (field (name "MFR PART #") "XL-5050RGBC-WS2812B")
        (field (name "MANUFACTURER") "XINGLIGHT")
      )
      (libsource (lib "ECEN5730Lib_2023_05_DS") (part "LED_Smart"))
    )
    (comp (ref "D27")
      (value "IN-PI55QATPRPGPBPW")
      (footprint "SERIAL_LED - duplicate")
      (fields
        (field (name "LCSC PART#") "C2843785")
        (field (name "MFR PART #") "XL-5050RGBC-WS2812B")
        (field (name "MANUFACTURER") "XINGLIGHT")
      )
      (libsource (lib "ECEN5730Lib_2023_05_DS") (part "LED_Smart"))
    )
    (comp (ref "D28")
      (value "IN-PI55QATPRPGPBPW")
      (footprint "SERIAL_LED - duplicate")
      (fields
        (field (name "LCSC PART#") "C2843785")
        (field (name "MFR PART #") "XL-5050RGBC-WS2812B")
        (field (name "MANUFACTURER") "XINGLIGHT")
      )
      (libsource (lib "ECEN5730Lib_2023_05_DS") (part "LED_Smart"))
    )
    (comp (ref "D29")
      (value "IN-PI55QATPRPGPBPW")
      (footprint "SERIAL_LED - duplicate")
      (fields
        (field (name "LCSC PART#") "C2843785")
        (field (name "MFR PART #") "XL-5050RGBC-WS2812B")
        (field (name "MANUFACTURER") "XINGLIGHT")
      )
      (libsource (lib "ECEN5730Lib_2023_05_DS") (part "LED_Smart"))
    )
    (comp (ref "D30")
      (value "IN-PI55QATPRPGPBPW")
      (footprint "SERIAL_LED - duplicate")
      (fields
        (field (name "LCSC PART#") "C2843785")
        (field (name "MFR PART #") "XL-5050RGBC-WS2812B")
        (field (name "MANUFACTURER") "XINGLIGHT")
      )
      (libsource (lib "ECEN5730Lib_2023_05_DS") (part "LED_Smart"))
    )
    (comp (ref "D31")
      (value "IN-PI55QATPRPGPBPW")
      (footprint "SERIAL_LED - duplicate")
      (fields
        (field (name "LCSC PART#") "C2843785")
        (field (name "MFR PART #") "XL-5050RGBC-WS2812B")
        (field (name "MANUFACTURER") "XINGLIGHT")
      )
      (libsource (lib "ECEN5730Lib_2023_05_DS") (part "LED_Smart"))
    )
    (comp (ref "D32")
      (value "IN-PI55QATPRPGPBPW")
      (footprint "SERIAL_LED - duplicate")
      (fields
        (field (name "LCSC PART#") "C2843785")
        (field (name "MFR PART #") "XL-5050RGBC-WS2812B")
        (field (name "MANUFACTURER") "XINGLIGHT")
      )
      (libsource (lib "ECEN5730Lib_2023_05_DS") (part "LED_Smart"))
    )
    (comp (ref "D33")
      (value "IN-PI55QATPRPGPBPW")
      (footprint "SERIAL_LED - duplicate")
      (fields
        (field (name "LCSC PART#") "C2843785")
        (field (name "MFR PART #") "XL-5050RGBC-WS2812B")
        (field (name "MANUFACTURER") "XINGLIGHT")
      )
      (libsource (lib "ECEN5730Lib_2023_05_DS") (part "LED_Smart"))
    )
    (comp (ref "D34")
      (value "IN-PI55QATPRPGPBPW")
      (footprint "SERIAL_LED - duplicate")
      (fields
        (field (name "LCSC PART#") "C2843785")
        (field (name "MFR PART #") "XL-5050RGBC-WS2812B")
        (field (name "MANUFACTURER") "XINGLIGHT")
      )
      (libsource (lib "ECEN5730Lib_2023_05_DS") (part "LED_Smart"))
    )
    (comp (ref "D35")
      (value "IN-PI55QATPRPGPBPW")
      (footprint "SERIAL_LED - duplicate")
      (fields
        (field (name "LCSC PART#") "C2843785")
        (field (name "MFR PART #") "XL-5050RGBC-WS2812B")
        (field (name "MANUFACTURER") "XINGLIGHT")
      )
      (libsource (lib "ECEN5730Lib_2023_05_DS") (part "LED_Smart"))
    )
    (comp (ref "D36")
      (value "IN-PI55QATPRPGPBPW")
      (footprint "SERIAL_LED - duplicate")
      (fields
        (field (name "LCSC PART#") "C2843785")
        (field (name "MFR PART #") "XL-5050RGBC-WS2812B")
        (field (name "MANUFACTURER") "XINGLIGHT")
      )
      (libsource (lib "ECEN5730Lib_2023_05_DS") (part "LED_Smart"))
    )
    (comp (ref "D37")
      (value "IN-PI55QATPRPGPBPW")
      (footprint "SERIAL_LED - duplicate")
      (fields
        (field (name "LCSC PART#") "C2843785")
        (field (name "MFR PART #") "XL-5050RGBC-WS2812B")
        (field (name "MANUFACTURER") "XINGLIGHT")
      )
      (libsource (lib "ECEN5730Lib_2023_05_DS") (part "LED_Smart"))
    )
    (comp (ref "D38")
      (value "IN-PI55QATPRPGPBPW")
      (footprint "SERIAL_LED - duplicate")
      (fields
        (field (name "LCSC PART#") "C2843785")
        (field (name "MFR PART #") "XL-5050RGBC-WS2812B")
        (field (name "MANUFACTURER") "XINGLIGHT")
      )
      (libsource (lib "ECEN5730Lib_2023_05_DS") (part "LED_Smart"))
    )
    (comp (ref "D39")
      (value "IN-PI55QATPRPGPBPW")
      (footprint "SERIAL_LED - duplicate")
      (fields
        (field (name "LCSC PART#") "C2843785")
        (field (name "MFR PART #") "XL-5050RGBC-WS2812B")
        (field (name "MANUFACTURER") "XINGLIGHT")
      )
      (libsource (lib "ECEN5730Lib_2023_05_DS") (part "LED_Smart"))
    )
    (comp (ref "D40")
      (value "IN-PI55QATPRPGPBPW")
      (footprint "SERIAL_LED - duplicate")
      (fields
        (field (name "LCSC PART#") "C2843785")
        (field (name "MFR PART #") "XL-5050RGBC-WS2812B")
        (field (name "MANUFACTURER") "XINGLIGHT")
      )
      (libsource (lib "ECEN5730Lib_2023_05_DS") (part "LED_Smart"))
    )
    (comp (ref "D41")
      (value "IN-PI55QATPRPGPBPW")
      (footprint "SERIAL_LED - duplicate")
      (fields
        (field (name "LCSC PART#") "C2843785")
        (field (name "MFR PART #") "XL-5050RGBC-WS2812B")
        (field (name "MANUFACTURER") "XINGLIGHT")
      )
      (libsource (lib "ECEN5730Lib_2023_05_DS") (part "LED_Smart"))
    )
    (comp (ref "D42")
      (value "IN-PI55QATPRPGPBPW")
      (footprint "SERIAL_LED - duplicate")
      (fields
        (field (name "LCSC PART#") "C2843785")
        (field (name "MFR PART #") "XL-5050RGBC-WS2812B")
        (field (name "MANUFACTURER") "XINGLIGHT")
      )
      (libsource (lib "ECEN5730Lib_2023_05_DS") (part "LED_Smart"))
    )
    (comp (ref "D43")
      (value "IN-PI55QATPRPGPBPW")
      (footprint "SERIAL_LED - duplicate")
      (fields
        (field (name "LCSC PART#") "C2843785")
        (field (name "MFR PART #") "XL-5050RGBC-WS2812B")
        (field (name "MANUFACTURER") "XINGLIGHT")
      )
      (libsource (lib "ECEN5730Lib_2023_05_DS") (part "LED_Smart"))
    )
    (comp (ref "D44")
      (value "IN-PI55QATPRPGPBPW")
      (footprint "SERIAL_LED - duplicate")
      (fields
        (field (name "LCSC PART#") "C2843785")
        (field (name "MFR PART #") "XL-5050RGBC-WS2812B")
        (field (name "MANUFACTURER") "XINGLIGHT")
      )
      (libsource (lib "ECEN5730Lib_2023_05_DS") (part "LED_Smart"))
    )
    (comp (ref "D45")
      (value "IN-PI55QATPRPGPBPW")
      (footprint "SERIAL_LED - duplicate")
      (fields
        (field (name "LCSC PART#") "C2843785")
        (field (name "MFR PART #") "XL-5050RGBC-WS2812B")
        (field (name "MANUFACTURER") "XINGLIGHT")
      )
      (libsource (lib "ECEN5730Lib_2023_05_DS") (part "LED_Smart"))
    )
    (comp (ref "D46")
      (value "IN-PI55QATPRPGPBPW")
      (footprint "SERIAL_LED - duplicate")
      (fields
        (field (name "LCSC PART#") "C2843785")
        (field (name "MFR PART #") "XL-5050RGBC-WS2812B")
        (field (name "MANUFACTURER") "XINGLIGHT")
      )
      (libsource (lib "ECEN5730Lib_2023_05_DS") (part "LED_Smart"))
    )
    (comp (ref "D47")
      (value "IN-PI55QATPRPGPBPW")
      (footprint "SERIAL_LED - duplicate")
      (fields
        (field (name "LCSC PART#") "C2843785")
        (field (name "MFR PART #") "XL-5050RGBC-WS2812B")
        (field (name "MANUFACTURER") "XINGLIGHT")
      )
      (libsource (lib "ECEN5730Lib_2023_05_DS") (part "LED_Smart"))
    )
    (comp (ref "D48")
      (value "IN-PI55QATPRPGPBPW")
      (footprint "SERIAL_LED - duplicate")
      (fields
        (field (name "LCSC PART#") "C2843785")
        (field (name "MFR PART #") "XL-5050RGBC-WS2812B")
        (field (name "MANUFACTURER") "XINGLIGHT")
      )
      (libsource (lib "ECEN5730Lib_2023_05_DS") (part "LED_Smart"))
    )
    (comp (ref "D49")
      (value "IN-PI55QATPRPGPBPW")
      (footprint "SERIAL_LED - duplicate")
      (fields
        (field (name "LCSC PART#") "C2843785")
        (field (name "MFR PART #") "XL-5050RGBC-WS2812B")
        (field (name "MANUFACTURER") "XINGLIGHT")
      )
      (libsource (lib "ECEN5730Lib_2023_05_DS") (part "LED_Smart"))
    )
    (comp (ref "D50")
      (value "IN-PI55QATPRPGPBPW")
      (footprint "SERIAL_LED - duplicate")
      (fields
        (field (name "LCSC PART#") "C2843785")
        (field (name "MFR PART #") "XL-5050RGBC-WS2812B")
        (field (name "MANUFACTURER") "XINGLIGHT")
      )
      (libsource (lib "ECEN5730Lib_2023_05_DS") (part "LED_Smart"))
    )
    (comp (ref "D51")
      (value "IN-PI55QATPRPGPBPW")
      (footprint "SERIAL_LED - duplicate")
      (fields
        (field (name "LCSC PART#") "C2843785")
        (field (name "MFR PART #") "XL-5050RGBC-WS2812B")
        (field (name "MANUFACTURER") "XINGLIGHT")
      )
      (libsource (lib "ECEN5730Lib_2023_05_DS") (part "LED_Smart"))
    )
    (comp (ref "D52")
      (value "IN-PI55QATPRPGPBPW")
      (footprint "SERIAL_LED - duplicate")
      (fields
        (field (name "LCSC PART#") "C2843785")
        (field (name "MFR PART #") "XL-5050RGBC-WS2812B")
        (field (name "MANUFACTURER") "XINGLIGHT")
      )
      (libsource (lib "ECEN5730Lib_2023_05_DS") (part "LED_Smart"))
    )
    (comp (ref "D53")
      (value "IN-PI55QATPRPGPBPW")
      (footprint "SERIAL_LED - duplicate")
      (fields
        (field (name "LCSC PART#") "C2843785")
        (field (name "MFR PART #") "XL-5050RGBC-WS2812B")
        (field (name "MANUFACTURER") "XINGLIGHT")
      )
      (libsource (lib "ECEN5730Lib_2023_05_DS") (part "LED_Smart"))
    )
    (comp (ref "D54")
      (value "IN-PI55QATPRPGPBPW")
      (footprint "SERIAL_LED - duplicate")
      (fields
        (field (name "LCSC PART#") "C2843785")
        (field (name "MFR PART #") "XL-5050RGBC-WS2812B")
        (field (name "MANUFACTURER") "XINGLIGHT")
      )
      (libsource (lib "ECEN5730Lib_2023_05_DS") (part "LED_Smart"))
    )
    (comp (ref "D55")
      (value "IN-PI55QATPRPGPBPW")
      (footprint "SERIAL_LED - duplicate")
      (fields
        (field (name "LCSC PART#") "C2843785")
        (field (name "MFR PART #") "XL-5050RGBC-WS2812B")
        (field (name "MANUFACTURER") "XINGLIGHT")
      )
      (libsource (lib "ECEN5730Lib_2023_05_DS") (part "LED_Smart"))
    )
    (comp (ref "D56")
      (value "IN-PI55QATPRPGPBPW")
      (footprint "SERIAL_LED - duplicate")
      (fields
        (field (name "LCSC PART#") "C2843785")
        (field (name "MFR PART #") "XL-5050RGBC-WS2812B")
        (field (name "MANUFACTURER") "XINGLIGHT")
      )
      (libsource (lib "ECEN5730Lib_2023_05_DS") (part "LED_Smart"))
    )
    (comp (ref "D57")
      (value "IN-PI55QATPRPGPBPW")
      (footprint "SERIAL_LED - duplicate")
      (fields
        (field (name "LCSC PART#") "C2843785")
        (field (name "MFR PART #") "XL-5050RGBC-WS2812B")
        (field (name "MANUFACTURER") "XINGLIGHT")
      )
      (libsource (lib "ECEN5730Lib_2023_05_DS") (part "LED_Smart"))
    )
    (comp (ref "D58")
      (value "IN-PI55QATPRPGPBPW")
      (footprint "SERIAL_LED - duplicate")
      (fields
        (field (name "LCSC PART#") "C2843785")
        (field (name "MFR PART #") "XL-5050RGBC-WS2812B")
        (field (name "MANUFACTURER") "XINGLIGHT")
      )
      (libsource (lib "ECEN5730Lib_2023_05_DS") (part "LED_Smart"))
    )
    (comp (ref "D59")
      (value "IN-PI55QATPRPGPBPW")
      (footprint "SERIAL_LED - duplicate")
      (fields
        (field (name "LCSC PART#") "C2843785")
        (field (name "MFR PART #") "XL-5050RGBC-WS2812B")
        (field (name "MANUFACTURER") "XINGLIGHT")
      )
      (libsource (lib "ECEN5730Lib_2023_05_DS") (part "LED_Smart"))
    )
    (comp (ref "D60")
      (value "IN-PI55QATPRPGPBPW")
      (footprint "SERIAL_LED - duplicate")
      (fields
        (field (name "LCSC PART#") "C2843785")
        (field (name "MFR PART #") "XL-5050RGBC-WS2812B")
        (field (name "MANUFACTURER") "XINGLIGHT")
      )
      (libsource (lib "ECEN5730Lib_2023_05_DS") (part "LED_Smart"))
    )
    (comp (ref "D61")
      (value "IN-PI55QATPRPGPBPW")
      (footprint "SERIAL_LED - duplicate")
      (fields
        (field (name "LCSC PART#") "C2843785")
        (field (name "MFR PART #") "XL-5050RGBC-WS2812B")
        (field (name "MANUFACTURER") "XINGLIGHT")
      )
      (libsource (lib "ECEN5730Lib_2023_05_DS") (part "LED_Smart"))
    )
    (comp (ref "D62")
      (value "IN-PI55QATPRPGPBPW")
      (footprint "SERIAL_LED - duplicate")
      (fields
        (field (name "LCSC PART#") "C2843785")
        (field (name "MFR PART #") "XL-5050RGBC-WS2812B")
        (field (name "MANUFACTURER") "XINGLIGHT")
      )
      (libsource (lib "ECEN5730Lib_2023_05_DS") (part "LED_Smart"))
    )
    (comp (ref "D63")
      (value "IN-PI55QATPRPGPBPW")
      (footprint "SERIAL_LED - duplicate")
      (fields
        (field (name "LCSC PART#") "C2843785")
        (field (name "MFR PART #") "XL-5050RGBC-WS2812B")
        (field (name "MANUFACTURER") "XINGLIGHT")
      )
      (libsource (lib "ECEN5730Lib_2023_05_DS") (part "LED_Smart"))
    )
    (comp (ref "D64")
      (value "IN-PI55QATPRPGPBPW")
      (footprint "SERIAL_LED - duplicate")
      (fields
        (field (name "LCSC PART#") "C2843785")
        (field (name "MFR PART #") "XL-5050RGBC-WS2812B")
        (field (name "MANUFACTURER") "XINGLIGHT")
      )
      (libsource (lib "ECEN5730Lib_2023_05_DS") (part "LED_Smart"))
    )
    (comp (ref "D65")
      (value "IN-PI55QATPRPGPBPW")
      (footprint "SERIAL_LED - duplicate")
      (fields
        (field (name "LCSC PART#") "C2843785")
        (field (name "MFR PART #") "XL-5050RGBC-WS2812B")
        (field (name "MANUFACTURER") "XINGLIGHT")
      )
      (libsource (lib "ECEN5730Lib_2023_05_DS") (part "LED_Smart"))
    )
    (comp (ref "D66")
      (value "IN-PI55QATPRPGPBPW")
      (footprint "SERIAL_LED - duplicate")
      (fields
        (field (name "LCSC PART#") "C2843785")
        (field (name "MFR PART #") "XL-5050RGBC-WS2812B")
        (field (name "MANUFACTURER") "XINGLIGHT")
      )
      (libsource (lib "ECEN5730Lib_2023_05_DS") (part "LED_Smart"))
    )
    (comp (ref "D67")
      (value "IN-PI55QATPRPGPBPW")
      (footprint "SERIAL_LED - duplicate")
      (fields
        (field (name "LCSC PART#") "C2843785")
        (field (name "MFR PART #") "XL-5050RGBC-WS2812B")
        (field (name "MANUFACTURER") "XINGLIGHT")
      )
      (libsource (lib "ECEN5730Lib_2023_05_DS") (part "LED_Smart"))
    )
    (comp (ref "D68")
      (value "IN-PI55QATPRPGPBPW")
      (footprint "SERIAL_LED - duplicate")
      (fields
        (field (name "LCSC PART#") "C2843785")
        (field (name "MFR PART #") "XL-5050RGBC-WS2812B")
        (field (name "MANUFACTURER") "XINGLIGHT")
      )
      (libsource (lib "ECEN5730Lib_2023_05_DS") (part "LED_Smart"))
    )
    (comp (ref "D69")
      (value "IN-PI55QATPRPGPBPW")
      (footprint "SERIAL_LED - duplicate")
      (fields
        (field (name "LCSC PART#") "C2843785")
        (field (name "MFR PART #") "XL-5050RGBC-WS2812B")
        (field (name "MANUFACTURER") "XINGLIGHT")
      )
      (libsource (lib "ECEN5730Lib_2023_05_DS") (part "LED_Smart"))
    )
    (comp (ref "D70")
      (value "IN-PI55QATPRPGPBPW")
      (footprint "SERIAL_LED - duplicate")
      (fields
        (field (name "LCSC PART#") "C2843785")
        (field (name "MFR PART #") "XL-5050RGBC-WS2812B")
        (field (name "MANUFACTURER") "XINGLIGHT")
      )
      (libsource (lib "ECEN5730Lib_2023_05_DS") (part "LED_Smart"))
    )
    (comp (ref "D71")
      (value "IN-PI55QATPRPGPBPW")
      (footprint "SERIAL_LED - duplicate")
      (fields
        (field (name "LCSC PART#") "C2843785")
        (field (name "MFR PART #") "XL-5050RGBC-WS2812B")
        (field (name "MANUFACTURER") "XINGLIGHT")
      )
      (libsource (lib "ECEN5730Lib_2023_05_DS") (part "LED_Smart"))
    )
    (comp (ref "D72")
      (value "IN-PI55QATPRPGPBPW")
      (footprint "SERIAL_LED - duplicate")
      (fields
        (field (name "LCSC PART#") "C2843785")
        (field (name "MFR PART #") "XL-5050RGBC-WS2812B")
        (field (name "MANUFACTURER") "XINGLIGHT")
      )
      (libsource (lib "ECEN5730Lib_2023_05_DS") (part "LED_Smart"))
    )
    (comp (ref "D73")
      (value "IN-PI55QATPRPGPBPW")
      (footprint "SERIAL_LED - duplicate")
      (fields
        (field (name "LCSC PART#") "C2843785")
        (field (name "MFR PART #") "XL-5050RGBC-WS2812B")
        (field (name "MANUFACTURER") "XINGLIGHT")
      )
      (libsource (lib "ECEN5730Lib_2023_05_DS") (part "LED_Smart"))
    )
    (comp (ref "D74")
      (value "IN-PI55QATPRPGPBPW")
      (footprint "SERIAL_LED - duplicate")
      (fields
        (field (name "LCSC PART#") "C2843785")
        (field (name "MFR PART #") "XL-5050RGBC-WS2812B")
        (field (name "MANUFACTURER") "XINGLIGHT")
      )
      (libsource (lib "ECEN5730Lib_2023_05_DS") (part "LED_Smart"))
    )
    (comp (ref "D75")
      (value "IN-PI55QATPRPGPBPW")
      (footprint "SERIAL_LED - duplicate")
      (fields
        (field (name "LCSC PART#") "C2843785")
        (field (name "MFR PART #") "XL-5050RGBC-WS2812B")
        (field (name "MANUFACTURER") "XINGLIGHT")
      )
      (libsource (lib "ECEN5730Lib_2023_05_DS") (part "LED_Smart"))
    )
    (comp (ref "D76")
      (value "IN-PI55QATPRPGPBPW")
      (footprint "SERIAL_LED - duplicate")
      (fields
        (field (name "LCSC PART#") "C2843785")
        (field (name "MFR PART #") "XL-5050RGBC-WS2812B")
        (field (name "MANUFACTURER") "XINGLIGHT")
      )
      (libsource (lib "ECEN5730Lib_2023_05_DS") (part "LED_Smart"))
    )
    (comp (ref "D77")
      (value "IN-PI55QATPRPGPBPW")
      (footprint "SERIAL_LED - duplicate")
      (fields
        (field (name "LCSC PART#") "C2843785")
        (field (name "MFR PART #") "XL-5050RGBC-WS2812B")
        (field (name "MANUFACTURER") "XINGLIGHT")
      )
      (libsource (lib "ECEN5730Lib_2023_05_DS") (part "LED_Smart"))
    )
    (comp (ref "D78")
      (value "IN-PI55QATPRPGPBPW")
      (footprint "SERIAL_LED - duplicate")
      (fields
        (field (name "LCSC PART#") "C2843785")
        (field (name "MFR PART #") "XL-5050RGBC-WS2812B")
        (field (name "MANUFACTURER") "XINGLIGHT")
      )
      (libsource (lib "ECEN5730Lib_2023_05_DS") (part "LED_Smart"))
    )
    (comp (ref "D79")
      (value "IN-PI55QATPRPGPBPW")
      (footprint "SERIAL_LED - duplicate")
      (fields
        (field (name "LCSC PART#") "C2843785")
        (field (name "MFR PART #") "XL-5050RGBC-WS2812B")
        (field (name "MANUFACTURER") "XINGLIGHT")
      )
      (libsource (lib "ECEN5730Lib_2023_05_DS") (part "LED_Smart"))
    )
    (comp (ref "D80")
      (value "IN-PI55QATPRPGPBPW")
      (footprint "SERIAL_LED - duplicate")
      (fields
        (field (name "LCSC PART#") "C2843785")
        (field (name "MFR PART #") "XL-5050RGBC-WS2812B")
        (field (name "MANUFACTURER") "XINGLIGHT")
      )
      (libsource (lib "ECEN5730Lib_2023_05_DS") (part "LED_Smart"))
    )
    (comp (ref "D81")
      (value "IN-PI55QATPRPGPBPW")
      (footprint "SERIAL_LED - duplicate")
      (fields
        (field (name "LCSC PART#") "C2843785")
        (field (name "MFR PART #") "XL-5050RGBC-WS2812B")
        (field (name "MANUFACTURER") "XINGLIGHT")
      )
      (libsource (lib "ECEN5730Lib_2023_05_DS") (part "LED_Smart"))
    )
    (comp (ref "D82")
      (value "IN-PI55QATPRPGPBPW")
      (footprint "SERIAL_LED - duplicate")
      (fields
        (field (name "LCSC PART#") "C2843785")
        (field (name "MFR PART #") "XL-5050RGBC-WS2812B")
        (field (name "MANUFACTURER") "XINGLIGHT")
      )
      (libsource (lib "ECEN5730Lib_2023_05_DS") (part "LED_Smart"))
    )
    (comp (ref "D83")
      (value "IN-PI55QATPRPGPBPW")
      (footprint "SERIAL_LED - duplicate")
      (fields
        (field (name "LCSC PART#") "C2843785")
        (field (name "MFR PART #") "XL-5050RGBC-WS2812B")
        (field (name "MANUFACTURER") "XINGLIGHT")
      )
      (libsource (lib "ECEN5730Lib_2023_05_DS") (part "LED_Smart"))
    )
    (comp (ref "D84")
      (value "IN-PI55QATPRPGPBPW")
      (footprint "SERIAL_LED - duplicate")
      (fields
        (field (name "LCSC PART#") "C2843785")
        (field (name "MFR PART #") "XL-5050RGBC-WS2812B")
        (field (name "MANUFACTURER") "XINGLIGHT")
      )
      (libsource (lib "ECEN5730Lib_2023_05_DS") (part "LED_Smart"))
    )
    (comp (ref "D85")
      (value "IN-PI55QATPRPGPBPW")
      (footprint "SERIAL_LED - duplicate")
      (fields
        (field (name "LCSC PART#") "C2843785")
        (field (name "MFR PART #") "XL-5050RGBC-WS2812B")
        (field (name "MANUFACTURER") "XINGLIGHT")
      )
      (libsource (lib "ECEN5730Lib_2023_05_DS") (part "LED_Smart"))
    )
    (comp (ref "D86")
      (value "IN-PI55QATPRPGPBPW")
      (footprint "SERIAL_LED - duplicate")
      (fields
        (field (name "LCSC PART#") "C2843785")
        (field (name "MFR PART #") "XL-5050RGBC-WS2812B")
        (field (name "MANUFACTURER") "XINGLIGHT")
      )
      (libsource (lib "ECEN5730Lib_2023_05_DS") (part "LED_Smart"))
    )
    (comp (ref "D87")
      (value "IN-PI55QATPRPGPBPW")
      (footprint "SERIAL_LED - duplicate")
      (fields
        (field (name "LCSC PART#") "C2843785")
        (field (name "MFR PART #") "XL-5050RGBC-WS2812B")
        (field (name "MANUFACTURER") "XINGLIGHT")
      )
      (libsource (lib "ECEN5730Lib_2023_05_DS") (part "LED_Smart"))
    )
    (comp (ref "D88")
      (value "IN-PI55QATPRPGPBPW")
      (footprint "SERIAL_LED - duplicate")
      (fields
        (field (name "LCSC PART#") "C2843785")
        (field (name "MFR PART #") "XL-5050RGBC-WS2812B")
        (field (name "MANUFACTURER") "XINGLIGHT")
      )
      (libsource (lib "ECEN5730Lib_2023_05_DS") (part "LED_Smart"))
    )
    (comp (ref "D89")
      (value "IN-PI55QATPRPGPBPW")
      (footprint "SERIAL_LED - duplicate")
      (fields
        (field (name "LCSC PART#") "C2843785")
        (field (name "MFR PART #") "XL-5050RGBC-WS2812B")
        (field (name "MANUFACTURER") "XINGLIGHT")
      )
      (libsource (lib "ECEN5730Lib_2023_05_DS") (part "LED_Smart"))
    )
    (comp (ref "D90")
      (value "IN-PI55QATPRPGPBPW")
      (footprint "SERIAL_LED - duplicate")
      (fields
        (field (name "LCSC PART#") "C2843785")
        (field (name "MFR PART #") "XL-5050RGBC-WS2812B")
        (field (name "MANUFACTURER") "XINGLIGHT")
      )
      (libsource (lib "ECEN5730Lib_2023_05_DS") (part "LED_Smart"))
    )
    (comp (ref "D91")
      (value "IN-PI55QATPRPGPBPW")
      (footprint "SERIAL_LED - duplicate")
      (fields
        (field (name "LCSC PART#") "C2843785")
        (field (name "MFR PART #") "XL-5050RGBC-WS2812B")
        (field (name "MANUFACTURER") "XINGLIGHT")
      )
      (libsource (lib "ECEN5730Lib_2023_05_DS") (part "LED_Smart"))
    )
    (comp (ref "D92")
      (value "IN-PI55QATPRPGPBPW")
      (footprint "SERIAL_LED - duplicate")
      (fields
        (field (name "LCSC PART#") "C2843785")
        (field (name "MFR PART #") "XL-5050RGBC-WS2812B")
        (field (name "MANUFACTURER") "XINGLIGHT")
      )
      (libsource (lib "ECEN5730Lib_2023_05_DS") (part "LED_Smart"))
    )
    (comp (ref "D93")
      (value "IN-PI55QATPRPGPBPW")
      (footprint "SERIAL_LED - duplicate")
      (fields
        (field (name "LCSC PART#") "C2843785")
        (field (name "MFR PART #") "XL-5050RGBC-WS2812B")
        (field (name "MANUFACTURER") "XINGLIGHT")
      )
      (libsource (lib "ECEN5730Lib_2023_05_DS") (part "LED_Smart"))
    )
    (comp (ref "D94")
      (value "IN-PI55QATPRPGPBPW")
      (footprint "SERIAL_LED - duplicate")
      (fields
        (field (name "LCSC PART#") "C2843785")
        (field (name "MFR PART #") "XL-5050RGBC-WS2812B")
        (field (name "MANUFACTURER") "XINGLIGHT")
      )
      (libsource (lib "ECEN5730Lib_2023_05_DS") (part "LED_Smart"))
    )
    (comp (ref "D95")
      (value "IN-PI55QATPRPGPBPW")
      (footprint "SERIAL_LED - duplicate")
      (fields
        (field (name "LCSC PART#") "C2843785")
        (field (name "MFR PART #") "XL-5050RGBC-WS2812B")
        (field (name "MANUFACTURER") "XINGLIGHT")
      )
      (libsource (lib "ECEN5730Lib_2023_05_DS") (part "LED_Smart"))
    )
    (comp (ref "D96")
      (value "IN-PI55QATPRPGPBPW")
      (footprint "SERIAL_LED - duplicate")
      (fields
        (field (name "LCSC PART#") "C2843785")
        (field (name "MFR PART #") "XL-5050RGBC-WS2812B")
        (field (name "MANUFACTURER") "XINGLIGHT")
      )
      (libsource (lib "ECEN5730Lib_2023_05_DS") (part "LED_Smart"))
    )
    (comp (ref "D97")
      (value "IN-PI55QATPRPGPBPW")
      (footprint "SERIAL_LED - duplicate")
      (fields
        (field (name "LCSC PART#") "C2843785")
        (field (name "MFR PART #") "XL-5050RGBC-WS2812B")
        (field (name "MANUFACTURER") "XINGLIGHT")
      )
      (libsource (lib "ECEN5730Lib_2023_05_DS") (part "LED_Smart"))
    )
    (comp (ref "D98")
      (value "IN-PI55QATPRPGPBPW")
      (footprint "SERIAL_LED - duplicate")
      (fields
        (field (name "LCSC PART#") "C2843785")
        (field (name "MFR PART #") "XL-5050RGBC-WS2812B")
        (field (name "MANUFACTURER") "XINGLIGHT")
      )
      (libsource (lib "ECEN5730Lib_2023_05_DS") (part "LED_Smart"))
    )
    (comp (ref "D99")
      (value "IN-PI55QATPRPGPBPW")
      (footprint "SERIAL_LED - duplicate")
      (fields
        (field (name "LCSC PART#") "C2843785")
        (field (name "MFR PART #") "XL-5050RGBC-WS2812B")
        (field (name "MANUFACTURER") "XINGLIGHT")
      )
      (libsource (lib "ECEN5730Lib_2023_05_DS") (part "LED_Smart"))
    )
    (comp (ref "D100")
      (value "IN-PI55QATPRPGPBPW")
      (footprint "SERIAL_LED - duplicate")
      (fields
        (field (name "LCSC PART#") "C2843785")
        (field (name "MFR PART #") "XL-5050RGBC-WS2812B")
        (field (name "MANUFACTURER") "XINGLIGHT")
      )
      (libsource (lib "ECEN5730Lib_2023_05_DS") (part "LED_Smart"))
    )
    (comp (ref "D101")
      (value "IN-PI55QATPRPGPBPW")
      (footprint "SERIAL_LED - duplicate")
      (fields
        (field (name "LCSC PART#") "C2843785")
        (field (name "MFR PART #") "XL-5050RGBC-WS2812B")
        (field (name "MANUFACTURER") "XINGLIGHT")
      )
      (libsource (lib "ECEN5730Lib_2023_05_DS") (part "LED_Smart"))
    )
    (comp (ref "D102")
      (value "IN-PI55QATPRPGPBPW")
      (footprint "SERIAL_LED - duplicate")
      (fields
        (field (name "LCSC PART#") "C2843785")
        (field (name "MFR PART #") "XL-5050RGBC-WS2812B")
        (field (name "MANUFACTURER") "XINGLIGHT")
      )
      (libsource (lib "ECEN5730Lib_2023_05_DS") (part "LED_Smart"))
    )
    (comp (ref "D103")
      (value "IN-PI55QATPRPGPBPW")
      (footprint "SERIAL_LED - duplicate")
      (fields
        (field (name "LCSC PART#") "C2843785")
        (field (name "MFR PART #") "XL-5050RGBC-WS2812B")
        (field (name "MANUFACTURER") "XINGLIGHT")
      )
      (libsource (lib "ECEN5730Lib_2023_05_DS") (part "LED_Smart"))
    )
    (comp (ref "D104")
      (value "IN-PI55QATPRPGPBPW")
      (footprint "SERIAL_LED - duplicate")
      (fields
        (field (name "LCSC PART#") "C2843785")
        (field (name "MFR PART #") "XL-5050RGBC-WS2812B")
        (field (name "MANUFACTURER") "XINGLIGHT")
      )
      (libsource (lib "ECEN5730Lib_2023_05_DS") (part "LED_Smart"))
    )
    (comp (ref "D105")
      (value "IN-PI55QATPRPGPBPW")
      (footprint "SERIAL_LED - duplicate")
      (fields
        (field (name "LCSC PART#") "C2843785")
        (field (name "MFR PART #") "XL-5050RGBC-WS2812B")
        (field (name "MANUFACTURER") "XINGLIGHT")
      )
      (libsource (lib "ECEN5730Lib_2023_05_DS") (part "LED_Smart"))
    )
    (comp (ref "D106")
      (value "IN-PI55QATPRPGPBPW")
      (footprint "SERIAL_LED - duplicate")
      (fields
        (field (name "LCSC PART#") "C2843785")
        (field (name "MFR PART #") "XL-5050RGBC-WS2812B")
        (field (name "MANUFACTURER") "XINGLIGHT")
      )
      (libsource (lib "ECEN5730Lib_2023_05_DS") (part "LED_Smart"))
    )
    (comp (ref "D107")
      (value "IN-PI55QATPRPGPBPW")
      (footprint "SERIAL_LED - duplicate")
      (fields
        (field (name "LCSC PART#") "C2843785")
        (field (name "MFR PART #") "XL-5050RGBC-WS2812B")
        (field (name "MANUFACTURER") "XINGLIGHT")
      )
      (libsource (lib "ECEN5730Lib_2023_05_DS") (part "LED_Smart"))
    )
    (comp (ref "D108")
      (value "IN-PI55QATPRPGPBPW")
      (footprint "SERIAL_LED - duplicate")
      (fields
        (field (name "LCSC PART#") "C2843785")
        (field (name "MFR PART #") "XL-5050RGBC-WS2812B")
        (field (name "MANUFACTURER") "XINGLIGHT")
      )
      (libsource (lib "ECEN5730Lib_2023_05_DS") (part "LED_Smart"))
    )
    (comp (ref "H1")
      (value "Stencil Hole")
      (footprint "AlignmentHole_1.5mm")
      (description "Stencil Allignment hole for use with 1.5mm pin")
      (libsource (lib "ECEN5730Lib_2023_05_DS") (part "H_StencilAllignment_1.5mm"))
    )
    (comp (ref "H2")
      (value "Stencil Hole")
      (footprint "AlignmentHole_1.5mm")
      (description "Stencil Allignment hole for use with 1.5mm pin")
      (libsource (lib "ECEN5730Lib_2023_05_DS") (part "H_StencilAllignment_1.5mm"))
    )
    (comp (ref "H3")
      (value "Stencil Hole")
      (footprint "AlignmentHole_1.5mm")
      (description "Stencil Allignment hole for use with 1.5mm pin")
      (libsource (lib "ECEN5730Lib_2023_05_DS") (part "H_StencilAllignment_1.5mm"))
    )
    (comp (ref "H4")
      (value "Stencil Hole")
      (footprint "AlignmentHole_1.5mm")
      (description "Stencil Allignment hole for use with 1.5mm pin")
      (libsource (lib "ECEN5730Lib_2023_05_DS") (part "H_StencilAllignment_1.5mm"))
    )
    (comp (ref "J1")
      (value "TSW-104-14-S-S")
      (footprint "JM-4_TSW-104-14-S-S")
      (description "Square Pins 2.5mm 6mm -40℃~+105℃ 1 4 3mm 2.54mm Black 1x4P Straight,P=2.54mm  Pin Headers ROHS")
      (fields (field (name "MFR PART #") "PZ254V-11-04P") (field (name "LCSC PART#") "C2691448"))
      (libsource (lib "ECEN5730Lib_2023_05_DS") (part "JM_4_PIN_MALE"))
    )
    (comp (ref "LED1")
      (value "Red")
      (footprint "LED_1206")
      (description "Red 621~631nm 1206 Light Emitting Diodes (LED) RoHS")
      (fields (field (name "MFR PART #") "15-21/R6C-FQ1R1B/2T") (field (name "LCSC PART#") "C93133"))
      (libsource (lib "ECEN5730Lib_2023_05_DS") (part "LED_RED_1206"))
    )
    (comp (ref "R1")
      (value "1K Ohm")
      (footprint "1206_Passive_Resitor")
      (description "CHIP RESISTOR - SURFACE MOUNT 1KOHMS ±1% 1/4W 1206 ROHS")
      (fields (field (name "MFR PART #") "RNCP1206FTD1K00CT") (field (name "LCSC PART#") "C4410"))
      (libsource (lib "ECEN5730Lib_2023_05_DS") (part "R_1K_1206"))
    )
    (comp (ref "TP1")
      (value "10x Probe TP")
      (footprint "TP10x_Probe")
      (description "Test Point 300 mil centers")
      (libsource (lib "ECEN5730Lib_2023_05_DS") (part "TP_10x_Probe"))
    )
    (comp (ref "TP2")
      (value "10x Probe TP")
      (footprint "TP10x_Probe")
      (description "Test Point 300 mil centers")
      (libsource (lib "ECEN5730Lib_2023_05_DS") (part "TP_10x_Probe"))
    )
    (comp (ref "TP3")
      (value "10x Probe TP")
      (footprint "TP10x_Probe")
      (description "Test Point 300 mil centers")
      (libsource (lib "") (part "TP_10x_Probe_1"))
    )
  )
  (nets
    (net (code "1") (name "+5") (class "Default")
      (node (ref "C1") (pin "2") (pinfunction "2_2") (pintype "passive"))
      (node (ref "C10") (pin "2") (pinfunction "2_2") (pintype "passive"))
      (node (ref "C100") (pin "2") (pinfunction "2_2") (pintype "passive"))
      (node (ref "C101") (pin "2") (pinfunction "2_2") (pintype "passive"))
      (node (ref "C102") (pin "2") (pinfunction "2_2") (pintype "passive"))
      (node (ref "C103") (pin "2") (pinfunction "2_2") (pintype "passive"))
      (node (ref "C104") (pin "2") (pinfunction "2_2") (pintype "passive"))
      (node (ref "C105") (pin "2") (pinfunction "2_2") (pintype "passive"))
      (node (ref "C106") (pin "2") (pinfunction "2_2") (pintype "passive"))
      (node (ref "C107") (pin "2") (pinfunction "2_2") (pintype "passive"))
      (node (ref "C108") (pin "2") (pinfunction "2_2") (pintype "passive"))
      (node (ref "C11") (pin "2") (pinfunction "2_2") (pintype "passive"))
      (node (ref "C12") (pin "2") (pinfunction "2_2") (pintype "passive"))
      (node (ref "C13") (pin "2") (pinfunction "2_2") (pintype "passive"))
      (node (ref "C14") (pin "2") (pinfunction "2_2") (pintype "passive"))
      (node (ref "C15") (pin "2") (pinfunction "2_2") (pintype "passive"))
      (node (ref "C16") (pin "2") (pinfunction "2_2") (pintype "passive"))
      (node (ref "C17") (pin "2") (pinfunction "2_2") (pintype "passive"))
      (node (ref "C18") (pin "2") (pinfunction "2_2") (pintype "passive"))
      (node (ref "C19") (pin "2") (pinfunction "2_2") (pintype "passive"))
      (node (ref "C2") (pin "2") (pinfunction "2_2") (pintype "passive"))
      (node (ref "C20") (pin "2") (pinfunction "2_2") (pintype "passive"))
      (node (ref "C21") (pin "2") (pinfunction "2_2") (pintype "passive"))
      (node (ref "C22") (pin "2") (pinfunction "2_2") (pintype "passive"))
      (node (ref "C23") (pin "2") (pinfunction "2_2") (pintype "passive"))
      (node (ref "C24") (pin "2") (pinfunction "2_2") (pintype "passive"))
      (node (ref "C25") (pin "2") (pinfunction "2_2") (pintype "passive"))
      (node (ref "C26") (pin "2") (pinfunction "2_2") (pintype "passive"))
      (node (ref "C27") (pin "2") (pinfunction "2_2") (pintype "passive"))
      (node (ref "C28") (pin "2") (pinfunction "2_2") (pintype "passive"))
      (node (ref "C29") (pin "2") (pinfunction "2_2") (pintype "passive"))
      (node (ref "C3") (pin "2") (pinfunction "2_2") (pintype "passive"))
      (node (ref "C30") (pin "2") (pinfunction "2_2") (pintype "passive"))
      (node (ref "C31") (pin "2") (pinfunction "2_2") (pintype "passive"))
      (node (ref "C32") (pin "2") (pinfunction "2_2") (pintype "passive"))
      (node (ref "C33") (pin "2") (pinfunction "2_2") (pintype "passive"))
      (node (ref "C34") (pin "2") (pinfunction "2_2") (pintype "passive"))
      (node (ref "C35") (pin "2") (pinfunction "2_2") (pintype "passive"))
      (node (ref "C36") (pin "2") (pinfunction "2_2") (pintype "passive"))
      (node (ref "C37") (pin "2") (pinfunction "2_2") (pintype "passive"))
      (node (ref "C38") (pin "2") (pinfunction "2_2") (pintype "passive"))
      (node (ref "C39") (pin "2") (pinfunction "2_2") (pintype "passive"))
      (node (ref "C4") (pin "2") (pinfunction "2_2") (pintype "passive"))
      (node (ref "C40") (pin "2") (pinfunction "2_2") (pintype "passive"))
      (node (ref "C41") (pin "2") (pinfunction "2_2") (pintype "passive"))
      (node (ref "C42") (pin "2") (pinfunction "2_2") (pintype "passive"))
      (node (ref "C43") (pin "2") (pinfunction "2_2") (pintype "passive"))
      (node (ref "C44") (pin "2") (pinfunction "2_2") (pintype "passive"))
      (node (ref "C45") (pin "2") (pinfunction "2_2") (pintype "passive"))
      (node (ref "C46") (pin "2") (pinfunction "2_2") (pintype "passive"))
      (node (ref "C47") (pin "2") (pinfunction "2_2") (pintype "passive"))
      (node (ref "C48") (pin "2") (pinfunction "2_2") (pintype "passive"))
      (node (ref "C49") (pin "2") (pinfunction "2_2") (pintype "passive"))
      (node (ref "C5") (pin "2") (pinfunction "2_2") (pintype "passive"))
      (node (ref "C50") (pin "2") (pinfunction "2_2") (pintype "passive"))
      (node (ref "C51") (pin "2") (pinfunction "2_2") (pintype "passive"))
      (node (ref "C52") (pin "2") (pinfunction "2_2") (pintype "passive"))
      (node (ref "C53") (pin "2") (pinfunction "2_2") (pintype "passive"))
      (node (ref "C54") (pin "2") (pinfunction "2_2") (pintype "passive"))
      (node (ref "C55") (pin "2") (pinfunction "2_2") (pintype "passive"))
      (node (ref "C56") (pin "2") (pinfunction "2_2") (pintype "passive"))
      (node (ref "C57") (pin "2") (pinfunction "2_2") (pintype "passive"))
      (node (ref "C58") (pin "2") (pinfunction "2_2") (pintype "passive"))
      (node (ref "C59") (pin "2") (pinfunction "2_2") (pintype "passive"))
      (node (ref "C6") (pin "2") (pinfunction "2_2") (pintype "passive"))
      (node (ref "C60") (pin "2") (pinfunction "2_2") (pintype "passive"))
      (node (ref "C61") (pin "2") (pinfunction "2_2") (pintype "passive"))
      (node (ref "C62") (pin "2") (pinfunction "2_2") (pintype "passive"))
      (node (ref "C63") (pin "2") (pinfunction "2_2") (pintype "passive"))
      (node (ref "C64") (pin "2") (pinfunction "2_2") (pintype "passive"))
      (node (ref "C65") (pin "2") (pinfunction "2_2") (pintype "passive"))
      (node (ref "C66") (pin "2") (pinfunction "2_2") (pintype "passive"))
      (node (ref "C67") (pin "2") (pinfunction "2_2") (pintype "passive"))
      (node (ref "C68") (pin "2") (pinfunction "2_2") (pintype "passive"))
      (node (ref "C69") (pin "2") (pinfunction "2_2") (pintype "passive"))
      (node (ref "C7") (pin "2") (pinfunction "2_2") (pintype "passive"))
      (node (ref "C70") (pin "2") (pinfunction "2_2") (pintype "passive"))
      (node (ref "C71") (pin "2") (pinfunction "2_2") (pintype "passive"))
      (node (ref "C72") (pin "2") (pinfunction "2_2") (pintype "passive"))
      (node (ref "C73") (pin "2") (pinfunction "2_2") (pintype "passive"))
      (node (ref "C74") (pin "2") (pinfunction "2_2") (pintype "passive"))
      (node (ref "C75") (pin "2") (pinfunction "2_2") (pintype "passive"))
      (node (ref "C76") (pin "2") (pinfunction "2_2") (pintype "passive"))
      (node (ref "C77") (pin "2") (pinfunction "2_2") (pintype "passive"))
      (node (ref "C78") (pin "2") (pinfunction "2_2") (pintype "passive"))
      (node (ref "C79") (pin "2") (pinfunction "2_2") (pintype "passive"))
      (node (ref "C8") (pin "2") (pinfunction "2_2") (pintype "passive"))
      (node (ref "C80") (pin "2") (pinfunction "2_2") (pintype "passive"))
      (node (ref "C81") (pin "2") (pinfunction "2_2") (pintype "passive"))
      (node (ref "C82") (pin "2") (pinfunction "2_2") (pintype "passive"))
      (node (ref "C83") (pin "2") (pinfunction "2_2") (pintype "passive"))
      (node (ref "C84") (pin "2") (pinfunction "2_2") (pintype "passive"))
      (node (ref "C85") (pin "2") (pinfunction "2_2") (pintype "passive"))
      (node (ref "C86") (pin "2") (pinfunction "2_2") (pintype "passive"))
      (node (ref "C87") (pin "2") (pinfunction "2_2") (pintype "passive"))
      (node (ref "C88") (pin "2") (pinfunction "2_2") (pintype "passive"))
      (node (ref "C89") (pin "2") (pinfunction "2_2") (pintype "passive"))
      (node (ref "C9") (pin "2") (pinfunction "2_2") (pintype "passive"))
      (node (ref "C90") (pin "2") (pinfunction "2_2") (pintype "passive"))
      (node (ref "C91") (pin "2") (pinfunction "2_2") (pintype "passive"))
      (node (ref "C92") (pin "2") (pinfunction "2_2") (pintype "passive"))
      (node (ref "C93") (pin "2") (pinfunction "2_2") (pintype "passive"))
      (node (ref "C94") (pin "2") (pinfunction "2_2") (pintype "passive"))
      (node (ref "C95") (pin "2") (pinfunction "2_2") (pintype "passive"))
      (node (ref "C96") (pin "2") (pinfunction "2_2") (pintype "passive"))
      (node (ref "C97") (pin "2") (pinfunction "2_2") (pintype "passive"))
      (node (ref "C98") (pin "2") (pinfunction "2_2") (pintype "passive"))
      (node (ref "C99") (pin "2") (pinfunction "2_2") (pintype "passive"))
      (node (ref "D1") (pin "1") (pinfunction "VDD_1") (pintype "input"))
      (node (ref "D10") (pin "1") (pinfunction "VDD_1") (pintype "input"))
      (node (ref "D100") (pin "1") (pinfunction "VDD_1") (pintype "input"))
      (node (ref "D101") (pin "1") (pinfunction "VDD_1") (pintype "input"))
      (node (ref "D102") (pin "1") (pinfunction "VDD_1") (pintype "input"))
      (node (ref "D103") (pin "1") (pinfunction "VDD_1") (pintype "input"))
      (node (ref "D104") (pin "1") (pinfunction "VDD_1") (pintype "input"))
      (node (ref "D105") (pin "1") (pinfunction "VDD_1") (pintype "input"))
      (node (ref "D106") (pin "1") (pinfunction "VDD_1") (pintype "input"))
      (node (ref "D107") (pin "1") (pinfunction "VDD_1") (pintype "input"))
      (node (ref "D108") (pin "1") (pinfunction "VDD_1") (pintype "input"))
      (node (ref "D11") (pin "1") (pinfunction "VDD_1") (pintype "input"))
      (node (ref "D12") (pin "1") (pinfunction "VDD_1") (pintype "input"))
      (node (ref "D13") (pin "1") (pinfunction "VDD_1") (pintype "input"))
      (node (ref "D14") (pin "1") (pinfunction "VDD_1") (pintype "input"))
      (node (ref "D15") (pin "1") (pinfunction "VDD_1") (pintype "input"))
      (node (ref "D16") (pin "1") (pinfunction "VDD_1") (pintype "input"))
      (node (ref "D17") (pin "1") (pinfunction "VDD_1") (pintype "input"))
      (node (ref "D18") (pin "1") (pinfunction "VDD_1") (pintype "input"))
      (node (ref "D19") (pin "1") (pinfunction "VDD_1") (pintype "input"))
      (node (ref "D2") (pin "1") (pinfunction "VDD_1") (pintype "input"))
      (node (ref "D20") (pin "1") (pinfunction "VDD_1") (pintype "input"))
      (node (ref "D21") (pin "1") (pinfunction "VDD_1") (pintype "input"))
      (node (ref "D22") (pin "1") (pinfunction "VDD_1") (pintype "input"))
      (node (ref "D23") (pin "1") (pinfunction "VDD_1") (pintype "input"))
      (node (ref "D24") (pin "1") (pinfunction "VDD_1") (pintype "input"))
      (node (ref "D25") (pin "1") (pinfunction "VDD_1") (pintype "input"))
      (node (ref "D26") (pin "1") (pinfunction "VDD_1") (pintype "input"))
      (node (ref "D27") (pin "1") (pinfunction "VDD_1") (pintype "input"))
      (node (ref "D28") (pin "1") (pinfunction "VDD_1") (pintype "input"))
      (node (ref "D29") (pin "1") (pinfunction "VDD_1") (pintype "input"))
      (node (ref "D3") (pin "1") (pinfunction "VDD_1") (pintype "input"))
      (node (ref "D30") (pin "1") (pinfunction "VDD_1") (pintype "input"))
      (node (ref "D31") (pin "1") (pinfunction "VDD_1") (pintype "input"))
      (node (ref "D32") (pin "1") (pinfunction "VDD_1") (pintype "input"))
      (node (ref "D33") (pin "1") (pinfunction "VDD_1") (pintype "input"))
      (node (ref "D34") (pin "1") (pinfunction "VDD_1") (pintype "input"))
      (node (ref "D35") (pin "1") (pinfunction "VDD_1") (pintype "input"))
      (node (ref "D36") (pin "1") (pinfunction "VDD_1") (pintype "input"))
      (node (ref "D37") (pin "1") (pinfunction "VDD_1") (pintype "input"))
      (node (ref "D38") (pin "1") (pinfunction "VDD_1") (pintype "input"))
      (node (ref "D39") (pin "1") (pinfunction "VDD_1") (pintype "input"))
      (node (ref "D4") (pin "1") (pinfunction "VDD_1") (pintype "input"))
      (node (ref "D40") (pin "1") (pinfunction "VDD_1") (pintype "input"))
      (node (ref "D41") (pin "1") (pinfunction "VDD_1") (pintype "input"))
      (node (ref "D42") (pin "1") (pinfunction "VDD_1") (pintype "input"))
      (node (ref "D43") (pin "1") (pinfunction "VDD_1") (pintype "input"))
      (node (ref "D44") (pin "1") (pinfunction "VDD_1") (pintype "input"))
      (node (ref "D45") (pin "1") (pinfunction "VDD_1") (pintype "input"))
      (node (ref "D46") (pin "1") (pinfunction "VDD_1") (pintype "input"))
      (node (ref "D47") (pin "1") (pinfunction "VDD_1") (pintype "input"))
      (node (ref "D48") (pin "1") (pinfunction "VDD_1") (pintype "input"))
      (node (ref "D49") (pin "1") (pinfunction "VDD_1") (pintype "input"))
      (node (ref "D5") (pin "1") (pinfunction "VDD_1") (pintype "input"))
      (node (ref "D50") (pin "1") (pinfunction "VDD_1") (pintype "input"))
      (node (ref "D51") (pin "1") (pinfunction "VDD_1") (pintype "input"))
      (node (ref "D52") (pin "1") (pinfunction "VDD_1") (pintype "input"))
      (node (ref "D53") (pin "1") (pinfunction "VDD_1") (pintype "input"))
      (node (ref "D54") (pin "1") (pinfunction "VDD_1") (pintype "input"))
      (node (ref "D55") (pin "1") (pinfunction "VDD_1") (pintype "input"))
      (node (ref "D56") (pin "1") (pinfunction "VDD_1") (pintype "input"))
      (node (ref "D57") (pin "1") (pinfunction "VDD_1") (pintype "input"))
      (node (ref "D58") (pin "1") (pinfunction "VDD_1") (pintype "input"))
      (node (ref "D59") (pin "1") (pinfunction "VDD_1") (pintype "input"))
      (node (ref "D6") (pin "1") (pinfunction "VDD_1") (pintype "input"))
      (node (ref "D60") (pin "1") (pinfunction "VDD_1") (pintype "input"))
      (node (ref "D61") (pin "1") (pinfunction "VDD_1") (pintype "input"))
      (node (ref "D62") (pin "1") (pinfunction "VDD_1") (pintype "input"))
      (node (ref "D63") (pin "1") (pinfunction "VDD_1") (pintype "input"))
      (node (ref "D64") (pin "1") (pinfunction "VDD_1") (pintype "input"))
      (node (ref "D65") (pin "1") (pinfunction "VDD_1") (pintype "input"))
      (node (ref "D66") (pin "1") (pinfunction "VDD_1") (pintype "input"))
      (node (ref "D67") (pin "1") (pinfunction "VDD_1") (pintype "input"))
      (node (ref "D68") (pin "1") (pinfunction "VDD_1") (pintype "input"))
      (node (ref "D69") (pin "1") (pinfunction "VDD_1") (pintype "input"))
      (node (ref "D7") (pin "1") (pinfunction "VDD_1") (pintype "input"))
      (node (ref "D70") (pin "1") (pinfunction "VDD_1") (pintype "input"))
      (node (ref "D71") (pin "1") (pinfunction "VDD_1") (pintype "input"))
      (node (ref "D72") (pin "1") (pinfunction "VDD_1") (pintype "input"))
      (node (ref "D73") (pin "1") (pinfunction "VDD_1") (pintype "input"))
      (node (ref "D74") (pin "1") (pinfunction "VDD_1") (pintype "input"))
      (node (ref "D75") (pin "1") (pinfunction "VDD_1") (pintype "input"))
      (node (ref "D76") (pin "1") (pinfunction "VDD_1") (pintype "input"))
      (node (ref "D77") (pin "1") (pinfunction "VDD_1") (pintype "input"))
      (node (ref "D78") (pin "1") (pinfunction "VDD_1") (pintype "input"))
      (node (ref "D79") (pin "1") (pinfunction "VDD_1") (pintype "input"))
      (node (ref "D8") (pin "1") (pinfunction "VDD_1") (pintype "input"))
      (node (ref "D80") (pin "1") (pinfunction "VDD_1") (pintype "input"))
      (node (ref "D81") (pin "1") (pinfunction "VDD_1") (pintype "input"))
      (node (ref "D82") (pin "1") (pinfunction "VDD_1") (pintype "input"))
      (node (ref "D83") (pin "1") (pinfunction "VDD_1") (pintype "input"))
      (node (ref "D84") (pin "1") (pinfunction "VDD_1") (pintype "input"))
      (node (ref "D85") (pin "1") (pinfunction "VDD_1") (pintype "input"))
      (node (ref "D86") (pin "1") (pinfunction "VDD_1") (pintype "input"))
      (node (ref "D87") (pin "1") (pinfunction "VDD_1") (pintype "input"))
      (node (ref "D88") (pin "1") (pinfunction "VDD_1") (pintype "input"))
      (node (ref "D89") (pin "1") (pinfunction "VDD_1") (pintype "input"))
      (node (ref "D9") (pin "1") (pinfunction "VDD_1") (pintype "input"))
      (node (ref "D90") (pin "1") (pinfunction "VDD_1") (pintype "input"))
      (node (ref "D91") (pin "1") (pinfunction "VDD_1") (pintype "input"))
      (node (ref "D92") (pin "1") (pinfunction "VDD_1") (pintype "input"))
      (node (ref "D93") (pin "1") (pinfunction "VDD_1") (pintype "input"))
      (node (ref "D94") (pin "1") (pinfunction "VDD_1") (pintype "input"))
      (node (ref "D95") (pin "1") (pinfunction "VDD_1") (pintype "input"))
      (node (ref "D96") (pin "1") (pinfunction "VDD_1") (pintype "input"))
      (node (ref "D97") (pin "1") (pinfunction "VDD_1") (pintype "input"))
      (node (ref "D98") (pin "1") (pinfunction "VDD_1") (pintype "input"))
      (node (ref "D99") (pin "1") (pinfunction "VDD_1") (pintype "input"))
      (node (ref "J1") (pin "01") (pinfunction "01_01") (pintype "passive"))
      (node (ref "R1") (pin "2") (pinfunction "2_2") (pintype "passive"))
      (node (ref "TP2") (pin "1") (pinfunction "Sgn_1") (pintype "passive"))
    )
    (net (code "3") (name "/STRIP2") (class "Default")
      (node (ref "D86") (pin "4") (pinfunction "DIN_4") (pintype "input"))
      (node (ref "J1") (pin "02") (pinfunction "02_02") (pintype "passive"))
      (node (ref "TP3") (pin "1") (pinfunction "Sgn_1") (pintype "passive"))
    )
    (net (code "4") (name "GND") (class "Default")
      (node (ref "C1") (pin "1") (pinfunction "1_1") (pintype "passive"))
      (node (ref "C10") (pin "1") (pinfunction "1_1") (pintype "passive"))
      (node (ref "C100") (pin "1") (pinfunction "1_1") (pintype "passive"))
      (node (ref "C101") (pin "1") (pinfunction "1_1") (pintype "passive"))
      (node (ref "C102") (pin "1") (pinfunction "1_1") (pintype "passive"))
      (node (ref "C103") (pin "1") (pinfunction "1_1") (pintype "passive"))
      (node (ref "C104") (pin "1") (pinfunction "1_1") (pintype "passive"))
      (node (ref "C105") (pin "1") (pinfunction "1_1") (pintype "passive"))
      (node (ref "C106") (pin "1") (pinfunction "1_1") (pintype "passive"))
      (node (ref "C107") (pin "1") (pinfunction "1_1") (pintype "passive"))
      (node (ref "C108") (pin "1") (pinfunction "1_1") (pintype "passive"))
      (node (ref "C11") (pin "1") (pinfunction "1_1") (pintype "passive"))
      (node (ref "C12") (pin "1") (pinfunction "1_1") (pintype "passive"))
      (node (ref "C13") (pin "1") (pinfunction "1_1") (pintype "passive"))
      (node (ref "C14") (pin "1") (pinfunction "1_1") (pintype "passive"))
      (node (ref "C15") (pin "1") (pinfunction "1_1") (pintype "passive"))
      (node (ref "C16") (pin "1") (pinfunction "1_1") (pintype "passive"))
      (node (ref "C17") (pin "1") (pinfunction "1_1") (pintype "passive"))
      (node (ref "C18") (pin "1") (pinfunction "1_1") (pintype "passive"))
      (node (ref "C19") (pin "1") (pinfunction "1_1") (pintype "passive"))
      (node (ref "C2") (pin "1") (pinfunction "1_1") (pintype "passive"))
      (node (ref "C20") (pin "1") (pinfunction "1_1") (pintype "passive"))
      (node (ref "C21") (pin "1") (pinfunction "1_1") (pintype "passive"))
      (node (ref "C22") (pin "1") (pinfunction "1_1") (pintype "passive"))
      (node (ref "C23") (pin "1") (pinfunction "1_1") (pintype "passive"))
      (node (ref "C24") (pin "1") (pinfunction "1_1") (pintype "passive"))
      (node (ref "C25") (pin "1") (pinfunction "1_1") (pintype "passive"))
      (node (ref "C26") (pin "1") (pinfunction "1_1") (pintype "passive"))
      (node (ref "C27") (pin "1") (pinfunction "1_1") (pintype "passive"))
      (node (ref "C28") (pin "1") (pinfunction "1_1") (pintype "passive"))
      (node (ref "C29") (pin "1") (pinfunction "1_1") (pintype "passive"))
      (node (ref "C3") (pin "1") (pinfunction "1_1") (pintype "passive"))
      (node (ref "C30") (pin "1") (pinfunction "1_1") (pintype "passive"))
      (node (ref "C31") (pin "1") (pinfunction "1_1") (pintype "passive"))
      (node (ref "C32") (pin "1") (pinfunction "1_1") (pintype "passive"))
      (node (ref "C33") (pin "1") (pinfunction "1_1") (pintype "passive"))
      (node (ref "C34") (pin "1") (pinfunction "1_1") (pintype "passive"))
      (node (ref "C35") (pin "1") (pinfunction "1_1") (pintype "passive"))
      (node (ref "C36") (pin "1") (pinfunction "1_1") (pintype "passive"))
      (node (ref "C37") (pin "1") (pinfunction "1_1") (pintype "passive"))
      (node (ref "C38") (pin "1") (pinfunction "1_1") (pintype "passive"))
      (node (ref "C39") (pin "1") (pinfunction "1_1") (pintype "passive"))
      (node (ref "C4") (pin "1") (pinfunction "1_1") (pintype "passive"))
      (node (ref "C40") (pin "1") (pinfunction "1_1") (pintype "passive"))
      (node (ref "C41") (pin "1") (pinfunction "1_1") (pintype "passive"))
      (node (ref "C42") (pin "1") (pinfunction "1_1") (pintype "passive"))
      (node (ref "C43") (pin "1") (pinfunction "1_1") (pintype "passive"))
      (node (ref "C44") (pin "1") (pinfunction "1_1") (pintype "passive"))
      (node (ref "C45") (pin "1") (pinfunction "1_1") (pintype "passive"))
      (node (ref "C46") (pin "1") (pinfunction "1_1") (pintype "passive"))
      (node (ref "C47") (pin "1") (pinfunction "1_1") (pintype "passive"))
      (node (ref "C48") (pin "1") (pinfunction "1_1") (pintype "passive"))
      (node (ref "C49") (pin "1") (pinfunction "1_1") (pintype "passive"))
      (node (ref "C5") (pin "1") (pinfunction "1_1") (pintype "passive"))
      (node (ref "C50") (pin "1") (pinfunction "1_1") (pintype "passive"))
      (node (ref "C51") (pin "1") (pinfunction "1_1") (pintype "passive"))
      (node (ref "C52") (pin "1") (pinfunction "1_1") (pintype "passive"))
      (node (ref "C53") (pin "1") (pinfunction "1_1") (pintype "passive"))
      (node (ref "C54") (pin "1") (pinfunction "1_1") (pintype "passive"))
      (node (ref "C55") (pin "1") (pinfunction "1_1") (pintype "passive"))
      (node (ref "C56") (pin "1") (pinfunction "1_1") (pintype "passive"))
      (node (ref "C57") (pin "1") (pinfunction "1_1") (pintype "passive"))
      (node (ref "C58") (pin "1") (pinfunction "1_1") (pintype "passive"))
      (node (ref "C59") (pin "1") (pinfunction "1_1") (pintype "passive"))
      (node (ref "C6") (pin "1") (pinfunction "1_1") (pintype "passive"))
      (node (ref "C60") (pin "1") (pinfunction "1_1") (pintype "passive"))
      (node (ref "C61") (pin "1") (pinfunction "1_1") (pintype "passive"))
      (node (ref "C62") (pin "1") (pinfunction "1_1") (pintype "passive"))
      (node (ref "C63") (pin "1") (pinfunction "1_1") (pintype "passive"))
      (node (ref "C64") (pin "1") (pinfunction "1_1") (pintype "passive"))
      (node (ref "C65") (pin "1") (pinfunction "1_1") (pintype "passive"))
      (node (ref "C66") (pin "1") (pinfunction "1_1") (pintype "passive"))
      (node (ref "C67") (pin "1") (pinfunction "1_1") (pintype "passive"))
      (node (ref "C68") (pin "1") (pinfunction "1_1") (pintype "passive"))
      (node (ref "C69") (pin "1") (pinfunction "1_1") (pintype "passive"))
      (node (ref "C7") (pin "1") (pinfunction "1_1") (pintype "passive"))
      (node (ref "C70") (pin "1") (pinfunction "1_1") (pintype "passive"))
      (node (ref "C71") (pin "1") (pinfunction "1_1") (pintype "passive"))
      (node (ref "C72") (pin "1") (pinfunction "1_1") (pintype "passive"))
      (node (ref "C73") (pin "1") (pinfunction "1_1") (pintype "passive"))
      (node (ref "C74") (pin "1") (pinfunction "1_1") (pintype "passive"))
      (node (ref "C75") (pin "1") (pinfunction "1_1") (pintype "passive"))
      (node (ref "C76") (pin "1") (pinfunction "1_1") (pintype "passive"))
      (node (ref "C77") (pin "1") (pinfunction "1_1") (pintype "passive"))
      (node (ref "C78") (pin "1") (pinfunction "1_1") (pintype "passive"))
      (node (ref "C79") (pin "1") (pinfunction "1_1") (pintype "passive"))
      (node (ref "C8") (pin "1") (pinfunction "1_1") (pintype "passive"))
      (node (ref "C80") (pin "1") (pinfunction "1_1") (pintype "passive"))
      (node (ref "C81") (pin "1") (pinfunction "1_1") (pintype "passive"))
      (node (ref "C82") (pin "1") (pinfunction "1_1") (pintype "passive"))
      (node (ref "C83") (pin "1") (pinfunction "1_1") (pintype "passive"))
      (node (ref "C84") (pin "1") (pinfunction "1_1") (pintype "passive"))
      (node (ref "C85") (pin "1") (pinfunction "1_1") (pintype "passive"))
      (node (ref "C86") (pin "1") (pinfunction "1_1") (pintype "passive"))
      (node (ref "C87") (pin "1") (pinfunction "1_1") (pintype "passive"))
      (node (ref "C88") (pin "1") (pinfunction "1_1") (pintype "passive"))
      (node (ref "C89") (pin "1") (pinfunction "1_1") (pintype "passive"))
      (node (ref "C9") (pin "1") (pinfunction "1_1") (pintype "passive"))
      (node (ref "C90") (pin "1") (pinfunction "1_1") (pintype "passive"))
      (node (ref "C91") (pin "1") (pinfunction "1_1") (pintype "passive"))
      (node (ref "C92") (pin "1") (pinfunction "1_1") (pintype "passive"))
      (node (ref "C93") (pin "1") (pinfunction "1_1") (pintype "passive"))
      (node (ref "C94") (pin "1") (pinfunction "1_1") (pintype "passive"))
      (node (ref "C95") (pin "1") (pinfunction "1_1") (pintype "passive"))
      (node (ref "C96") (pin "1") (pinfunction "1_1") (pintype "passive"))
      (node (ref "C97") (pin "1") (pinfunction "1_1") (pintype "passive"))
      (node (ref "C98") (pin "1") (pinfunction "1_1") (pintype "passive"))
      (node (ref "C99") (pin "1") (pinfunction "1_1") (pintype "passive"))
      (node (ref "D1") (pin "3") (pinfunction "VSS_3") (pintype "input"))
      (node (ref "D10") (pin "3") (pinfunction "VSS_3") (pintype "input"))
      (node (ref "D100") (pin "3") (pinfunction "VSS_3") (pintype "input"))
      (node (ref "D101") (pin "3") (pinfunction "VSS_3") (pintype "input"))
      (node (ref "D102") (pin "3") (pinfunction "VSS_3") (pintype "input"))
      (node (ref "D103") (pin "3") (pinfunction "VSS_3") (pintype "input"))
      (node (ref "D104") (pin "3") (pinfunction "VSS_3") (pintype "input"))
      (node (ref "D105") (pin "3") (pinfunction "VSS_3") (pintype "input"))
      (node (ref "D106") (pin "3") (pinfunction "VSS_3") (pintype "input"))
      (node (ref "D107") (pin "3") (pinfunction "VSS_3") (pintype "input"))
      (node (ref "D108") (pin "3") (pinfunction "VSS_3") (pintype "input"))
      (node (ref "D11") (pin "3") (pinfunction "VSS_3") (pintype "input"))
      (node (ref "D12") (pin "3") (pinfunction "VSS_3") (pintype "input"))
      (node (ref "D13") (pin "3") (pinfunction "VSS_3") (pintype "input"))
      (node (ref "D14") (pin "3") (pinfunction "VSS_3") (pintype "input"))
      (node (ref "D15") (pin "3") (pinfunction "VSS_3") (pintype "input"))
      (node (ref "D16") (pin "3") (pinfunction "VSS_3") (pintype "input"))
      (node (ref "D17") (pin "3") (pinfunction "VSS_3") (pintype "input"))
      (node (ref "D18") (pin "3") (pinfunction "VSS_3") (pintype "input"))
      (node (ref "D19") (pin "3") (pinfunction "VSS_3") (pintype "input"))
      (node (ref "D2") (pin "3") (pinfunction "VSS_3") (pintype "input"))
      (node (ref "D20") (pin "3") (pinfunction "VSS_3") (pintype "input"))
      (node (ref "D21") (pin "3") (pinfunction "VSS_3") (pintype "input"))
      (node (ref "D22") (pin "3") (pinfunction "VSS_3") (pintype "input"))
      (node (ref "D23") (pin "3") (pinfunction "VSS_3") (pintype "input"))
      (node (ref "D24") (pin "3") (pinfunction "VSS_3") (pintype "input"))
      (node (ref "D25") (pin "3") (pinfunction "VSS_3") (pintype "input"))
      (node (ref "D26") (pin "3") (pinfunction "VSS_3") (pintype "input"))
      (node (ref "D27") (pin "3") (pinfunction "VSS_3") (pintype "input"))
      (node (ref "D28") (pin "3") (pinfunction "VSS_3") (pintype "input"))
      (node (ref "D29") (pin "3") (pinfunction "VSS_3") (pintype "input"))
      (node (ref "D3") (pin "3") (pinfunction "VSS_3") (pintype "input"))
      (node (ref "D30") (pin "3") (pinfunction "VSS_3") (pintype "input"))
      (node (ref "D31") (pin "3") (pinfunction "VSS_3") (pintype "input"))
      (node (ref "D32") (pin "3") (pinfunction "VSS_3") (pintype "input"))
      (node (ref "D33") (pin "3") (pinfunction "VSS_3") (pintype "input"))
      (node (ref "D34") (pin "3") (pinfunction "VSS_3") (pintype "input"))
      (node (ref "D35") (pin "3") (pinfunction "VSS_3") (pintype "input"))
      (node (ref "D36") (pin "3") (pinfunction "VSS_3") (pintype "input"))
      (node (ref "D37") (pin "3") (pinfunction "VSS_3") (pintype "input"))
      (node (ref "D38") (pin "3") (pinfunction "VSS_3") (pintype "input"))
      (node (ref "D39") (pin "3") (pinfunction "VSS_3") (pintype "input"))
      (node (ref "D4") (pin "3") (pinfunction "VSS_3") (pintype "input"))
      (node (ref "D40") (pin "3") (pinfunction "VSS_3") (pintype "input"))
      (node (ref "D41") (pin "3") (pinfunction "VSS_3") (pintype "input"))
      (node (ref "D42") (pin "3") (pinfunction "VSS_3") (pintype "input"))
      (node (ref "D43") (pin "3") (pinfunction "VSS_3") (pintype "input"))
      (node (ref "D44") (pin "3") (pinfunction "VSS_3") (pintype "input"))
      (node (ref "D45") (pin "3") (pinfunction "VSS_3") (pintype "input"))
      (node (ref "D46") (pin "3") (pinfunction "VSS_3") (pintype "input"))
      (node (ref "D47") (pin "3") (pinfunction "VSS_3") (pintype "input"))
      (node (ref "D48") (pin "3") (pinfunction "VSS_3") (pintype "input"))
      (node (ref "D49") (pin "3") (pinfunction "VSS_3") (pintype "input"))
      (node (ref "D5") (pin "3") (pinfunction "VSS_3") (pintype "input"))
      (node (ref "D50") (pin "3") (pinfunction "VSS_3") (pintype "input"))
      (node (ref "D51") (pin "3") (pinfunction "VSS_3") (pintype "input"))
      (node (ref "D52") (pin "3") (pinfunction "VSS_3") (pintype "input"))
      (node (ref "D53") (pin "3") (pinfunction "VSS_3") (pintype "input"))
      (node (ref "D54") (pin "3") (pinfunction "VSS_3") (pintype "input"))
      (node (ref "D55") (pin "3") (pinfunction "VSS_3") (pintype "input"))
      (node (ref "D56") (pin "3") (pinfunction "VSS_3") (pintype "input"))
      (node (ref "D57") (pin "3") (pinfunction "VSS_3") (pintype "input"))
      (node (ref "D58") (pin "3") (pinfunction "VSS_3") (pintype "input"))
      (node (ref "D59") (pin "3") (pinfunction "VSS_3") (pintype "input"))
      (node (ref "D6") (pin "3") (pinfunction "VSS_3") (pintype "input"))
      (node (ref "D60") (pin "3") (pinfunction "VSS_3") (pintype "input"))
      (node (ref "D61") (pin "3") (pinfunction "VSS_3") (pintype "input"))
      (node (ref "D62") (pin "3") (pinfunction "VSS_3") (pintype "input"))
      (node (ref "D63") (pin "3") (pinfunction "VSS_3") (pintype "input"))
      (node (ref "D64") (pin "3") (pinfunction "VSS_3") (pintype "input"))
      (node (ref "D65") (pin "3") (pinfunction "VSS_3") (pintype "input"))
      (node (ref "D66") (pin "3") (pinfunction "VSS_3") (pintype "input"))
      (node (ref "D67") (pin "3") (pinfunction "VSS_3") (pintype "input"))
      (node (ref "D68") (pin "3") (pinfunction "VSS_3") (pintype "input"))
      (node (ref "D69") (pin "3") (pinfunction "VSS_3") (pintype "input"))
      (node (ref "D7") (pin "3") (pinfunction "VSS_3") (pintype "input"))
      (node (ref "D70") (pin "3") (pinfunction "VSS_3") (pintype "input"))
      (node (ref "D71") (pin "3") (pinfunction "VSS_3") (pintype "input"))
      (node (ref "D72") (pin "3") (pinfunction "VSS_3") (pintype "input"))
      (node (ref "D73") (pin "3") (pinfunction "VSS_3") (pintype "input"))
      (node (ref "D74") (pin "3") (pinfunction "VSS_3") (pintype "input"))
      (node (ref "D75") (pin "3") (pinfunction "VSS_3") (pintype "input"))
      (node (ref "D76") (pin "3") (pinfunction "VSS_3") (pintype "input"))
      (node (ref "D77") (pin "3") (pinfunction "VSS_3") (pintype "input"))
      (node (ref "D78") (pin "3") (pinfunction "VSS_3") (pintype "input"))
      (node (ref "D79") (pin "3") (pinfunction "VSS_3") (pintype "input"))
      (node (ref "D8") (pin "3") (pinfunction "VSS_3") (pintype "input"))
      (node (ref "D80") (pin "3") (pinfunction "VSS_3") (pintype "input"))
      (node (ref "D81") (pin "3") (pinfunction "VSS_3") (pintype "input"))
      (node (ref "D82") (pin "3") (pinfunction "VSS_3") (pintype "input"))
      (node (ref "D83") (pin "3") (pinfunction "VSS_3") (pintype "input"))
      (node (ref "D84") (pin "3") (pinfunction "VSS_3") (pintype "input"))
      (node (ref "D85") (pin "3") (pinfunction "VSS_3") (pintype "input"))
      (node (ref "D86") (pin "3") (pinfunction "VSS_3") (pintype "input"))
      (node (ref "D87") (pin "3") (pinfunction "VSS_3") (pintype "input"))
      (node (ref "D88") (pin "3") (pinfunction "VSS_3") (pintype "input"))
      (node (ref "D89") (pin "3") (pinfunction "VSS_3") (pintype "input"))
      (node (ref "D9") (pin "3") (pinfunction "VSS_3") (pintype "input"))
      (node (ref "D90") (pin "3") (pinfunction "VSS_3") (pintype "input"))
      (node (ref "D91") (pin "3") (pinfunction "VSS_3") (pintype "input"))
      (node (ref "D92") (pin "3") (pinfunction "VSS_3") (pintype "input"))
      (node (ref "D93") (pin "3") (pinfunction "VSS_3") (pintype "input"))
      (node (ref "D94") (pin "3") (pinfunction "VSS_3") (pintype "input"))
      (node (ref "D95") (pin "3") (pinfunction "VSS_3") (pintype "input"))
      (node (ref "D96") (pin "3") (pinfunction "VSS_3") (pintype "input"))
      (node (ref "D97") (pin "3") (pinfunction "VSS_3") (pintype "input"))
      (node (ref "D98") (pin "3") (pinfunction "VSS_3") (pintype "input"))
      (node (ref "D99") (pin "3") (pinfunction "VSS_3") (pintype "input"))
      (node (ref "J1") (pin "04") (pinfunction "04_04") (pintype "passive"))
      (node (ref "LED1") (pin "2") (pinfunction "2_2") (pintype "passive"))
      (node (ref "TP1") (pin "2") (pinfunction "Gnd_2") (pintype "passive"))
      (node (ref "TP2") (pin "2") (pinfunction "Gnd_2") (pintype "passive"))
      (node (ref "TP3") (pin "2") (pinfunction "Gnd_2") (pintype "passive"))
    )
    (net (code "5") (name "Net-(D1-DIN)") (class "Default")
      (node (ref "D1") (pin "4") (pinfunction "DIN_4") (pintype "input"))
      (node (ref "J1") (pin "03") (pinfunction "03_03") (pintype "passive"))
      (node (ref "TP1") (pin "1") (pinfunction "Sgn_1") (pintype "passive"))
    )
    (net (code "6") (name "Net-(D1-DOUT)") (class "Default")
      (node (ref "D1") (pin "2") (pinfunction "DOUT_2") (pintype "output"))
      (node (ref "D2") (pin "4") (pinfunction "DIN_4") (pintype "input"))
    )
    (net (code "7") (name "Net-(D2-DOUT)") (class "Default")
      (node (ref "D2") (pin "2") (pinfunction "DOUT_2") (pintype "output"))
      (node (ref "D3") (pin "4") (pinfunction "DIN_4") (pintype "input"))
    )
    (net (code "8") (name "Net-(D3-DOUT)") (class "Default")
      (node (ref "D3") (pin "2") (pinfunction "DOUT_2") (pintype "output"))
      (node (ref "D4") (pin "4") (pinfunction "DIN_4") (pintype "input"))
    )
    (net (code "9") (name "Net-(D4-DOUT)") (class "Default")
      (node (ref "D4") (pin "2") (pinfunction "DOUT_2") (pintype "output"))
      (node (ref "D5") (pin "4") (pinfunction "DIN_4") (pintype "input"))
    )
    (net (code "10") (name "Net-(D5-DOUT)") (class "Default")
      (node (ref "D5") (pin "2") (pinfunction "DOUT_2") (pintype "output"))
      (node (ref "D6") (pin "4") (pinfunction "DIN_4") (pintype "input"))
    )
    (net (code "11") (name "Net-(D6-DOUT)") (class "Default")
      (node (ref "D6") (pin "2") (pinfunction "DOUT_2") (pintype "output"))
      (node (ref "D7") (pin "4") (pinfunction "DIN_4") (pintype "input"))
    )
    (net (code "12") (name "Net-(D7-DOUT)") (class "Default")
      (node (ref "D7") (pin "2") (pinfunction "DOUT_2") (pintype "output"))
      (node (ref "D8") (pin "4") (pinfunction "DIN_4") (pintype "input"))
    )
    (net (code "13") (name "Net-(D8-DOUT)") (class "Default")
      (node (ref "D8") (pin "2") (pinfunction "DOUT_2") (pintype "output"))
      (node (ref "D9") (pin "4") (pinfunction "DIN_4") (pintype "input"))
    )
    (net (code "14") (name "Net-(D10-DIN)") (class "Default")
      (node (ref "D10") (pin "4") (pinfunction "DIN_4") (pintype "input"))
      (node (ref "D9") (pin "2") (pinfunction "DOUT_2") (pintype "output"))
    )
    (net (code "15") (name "Net-(D10-DOUT)") (class "Default")
      (node (ref "D10") (pin "2") (pinfunction "DOUT_2") (pintype "output"))
      (node (ref "D11") (pin "4") (pinfunction "DIN_4") (pintype "input"))
    )
    (net (code "16") (name "Net-(D11-DOUT)") (class "Default")
      (node (ref "D11") (pin "2") (pinfunction "DOUT_2") (pintype "output"))
      (node (ref "D12") (pin "4") (pinfunction "DIN_4") (pintype "input"))
    )
    (net (code "17") (name "Net-(D12-DOUT)") (class "Default")
      (node (ref "D12") (pin "2") (pinfunction "DOUT_2") (pintype "output"))
      (node (ref "D13") (pin "4") (pinfunction "DIN_4") (pintype "input"))
    )
    (net (code "18") (name "Net-(D13-DOUT)") (class "Default")
      (node (ref "D13") (pin "2") (pinfunction "DOUT_2") (pintype "output"))
      (node (ref "D14") (pin "4") (pinfunction "DIN_4") (pintype "input"))
    )
    (net (code "19") (name "Net-(D14-DOUT)") (class "Default")
      (node (ref "D14") (pin "2") (pinfunction "DOUT_2") (pintype "output"))
      (node (ref "D15") (pin "4") (pinfunction "DIN_4") (pintype "input"))
    )
    (net (code "20") (name "Net-(D15-DOUT)") (class "Default")
      (node (ref "D15") (pin "2") (pinfunction "DOUT_2") (pintype "output"))
      (node (ref "D16") (pin "4") (pinfunction "DIN_4") (pintype "input"))
    )
    (net (code "21") (name "Net-(D16-DOUT)") (class "Default")
      (node (ref "D16") (pin "2") (pinfunction "DOUT_2") (pintype "output"))
      (node (ref "D17") (pin "4") (pinfunction "DIN_4") (pintype "input"))
    )
    (net (code "22") (name "Net-(D17-DOUT)") (class "Default")
      (node (ref "D17") (pin "2") (pinfunction "DOUT_2") (pintype "output"))
      (node (ref "D18") (pin "4") (pinfunction "DIN_4") (pintype "input"))
    )
    (net (code "23") (name "Net-(D18-DOUT)") (class "Default")
      (node (ref "D18") (pin "2") (pinfunction "DOUT_2") (pintype "output"))
      (node (ref "D19") (pin "4") (pinfunction "DIN_4") (pintype "input"))
    )
    (net (code "24") (name "Net-(D19-DOUT)") (class "Default")
      (node (ref "D19") (pin "2") (pinfunction "DOUT_2") (pintype "output"))
      (node (ref "D20") (pin "4") (pinfunction "DIN_4") (pintype "input"))
    )
    (net (code "25") (name "Net-(D20-DOUT)") (class "Default")
      (node (ref "D20") (pin "2") (pinfunction "DOUT_2") (pintype "output"))
      (node (ref "D21") (pin "4") (pinfunction "DIN_4") (pintype "input"))
    )
    (net (code "26") (name "Net-(D21-DOUT)") (class "Default")
      (node (ref "D21") (pin "2") (pinfunction "DOUT_2") (pintype "output"))
      (node (ref "D22") (pin "4") (pinfunction "DIN_4") (pintype "input"))
    )
    (net (code "27") (name "Net-(D22-DOUT)") (class "Default")
      (node (ref "D22") (pin "2") (pinfunction "DOUT_2") (pintype "output"))
      (node (ref "D23") (pin "4") (pinfunction "DIN_4") (pintype "input"))
    )
    (net (code "28") (name "Net-(D23-DOUT)") (class "Default")
      (node (ref "D23") (pin "2") (pinfunction "DOUT_2") (pintype "output"))
      (node (ref "D24") (pin "4") (pinfunction "DIN_4") (pintype "input"))
    )
    (net (code "29") (name "Net-(D24-DOUT)") (class "Default")
      (node (ref "D24") (pin "2") (pinfunction "DOUT_2") (pintype "output"))
      (node (ref "D25") (pin "4") (pinfunction "DIN_4") (pintype "input"))
    )
    (net (code "30") (name "Net-(D25-DOUT)") (class "Default")
      (node (ref "D25") (pin "2") (pinfunction "DOUT_2") (pintype "output"))
      (node (ref "D26") (pin "4") (pinfunction "DIN_4") (pintype "input"))
    )
    (net (code "31") (name "Net-(D26-DOUT)") (class "Default")
      (node (ref "D26") (pin "2") (pinfunction "DOUT_2") (pintype "output"))
      (node (ref "D27") (pin "4") (pinfunction "DIN_4") (pintype "input"))
    )
    (net (code "32") (name "Net-(D27-DOUT)") (class "Default")
      (node (ref "D27") (pin "2") (pinfunction "DOUT_2") (pintype "output"))
      (node (ref "D28") (pin "4") (pinfunction "DIN_4") (pintype "input"))
    )
    (net (code "33") (name "Net-(D28-DOUT)") (class "Default")
      (node (ref "D28") (pin "2") (pinfunction "DOUT_2") (pintype "output"))
      (node (ref "D29") (pin "4") (pinfunction "DIN_4") (pintype "input"))
    )
    (net (code "34") (name "Net-(D29-DOUT)") (class "Default")
      (node (ref "D29") (pin "2") (pinfunction "DOUT_2") (pintype "output"))
      (node (ref "D30") (pin "4") (pinfunction "DIN_4") (pintype "input"))
    )
    (net (code "35") (name "Net-(D30-DOUT)") (class "Default")
      (node (ref "D30") (pin "2") (pinfunction "DOUT_2") (pintype "output"))
      (node (ref "D31") (pin "4") (pinfunction "DIN_4") (pintype "input"))
    )
    (net (code "36") (name "Net-(D31-DOUT)") (class "Default")
      (node (ref "D31") (pin "2") (pinfunction "DOUT_2") (pintype "output"))
      (node (ref "D32") (pin "4") (pinfunction "DIN_4") (pintype "input"))
    )
    (net (code "37") (name "Net-(D32-DOUT)") (class "Default")
      (node (ref "D32") (pin "2") (pinfunction "DOUT_2") (pintype "output"))
      (node (ref "D33") (pin "4") (pinfunction "DIN_4") (pintype "input"))
    )
    (net (code "38") (name "Net-(D33-DOUT)") (class "Default")
      (node (ref "D33") (pin "2") (pinfunction "DOUT_2") (pintype "output"))
      (node (ref "D34") (pin "4") (pinfunction "DIN_4") (pintype "input"))
    )
    (net (code "39") (name "Net-(D34-DOUT)") (class "Default")
      (node (ref "D34") (pin "2") (pinfunction "DOUT_2") (pintype "output"))
      (node (ref "D35") (pin "4") (pinfunction "DIN_4") (pintype "input"))
    )
    (net (code "40") (name "Net-(D35-DOUT)") (class "Default")
      (node (ref "D35") (pin "2") (pinfunction "DOUT_2") (pintype "output"))
      (node (ref "D36") (pin "4") (pinfunction "DIN_4") (pintype "input"))
    )
    (net (code "41") (name "Net-(D36-DOUT)") (class "Default")
      (node (ref "D36") (pin "2") (pinfunction "DOUT_2") (pintype "output"))
      (node (ref "D37") (pin "4") (pinfunction "DIN_4") (pintype "input"))
    )
    (net (code "42") (name "Net-(D37-DOUT)") (class "Default")
      (node (ref "D37") (pin "2") (pinfunction "DOUT_2") (pintype "output"))
      (node (ref "D38") (pin "4") (pinfunction "DIN_4") (pintype "input"))
    )
    (net (code "43") (name "Net-(D38-DOUT)") (class "Default")
      (node (ref "D38") (pin "2") (pinfunction "DOUT_2") (pintype "output"))
      (node (ref "D39") (pin "4") (pinfunction "DIN_4") (pintype "input"))
    )
    (net (code "44") (name "Net-(D39-DOUT)") (class "Default")
      (node (ref "D39") (pin "2") (pinfunction "DOUT_2") (pintype "output"))
      (node (ref "D40") (pin "4") (pinfunction "DIN_4") (pintype "input"))
    )
    (net (code "45") (name "Net-(D40-DOUT)") (class "Default")
      (node (ref "D40") (pin "2") (pinfunction "DOUT_2") (pintype "output"))
      (node (ref "D41") (pin "4") (pinfunction "DIN_4") (pintype "input"))
    )
    (net (code "46") (name "Net-(D41-DOUT)") (class "Default")
      (node (ref "D41") (pin "2") (pinfunction "DOUT_2") (pintype "output"))
      (node (ref "D42") (pin "4") (pinfunction "DIN_4") (pintype "input"))
    )
    (net (code "47") (name "Net-(D42-DOUT)") (class "Default")
      (node (ref "D42") (pin "2") (pinfunction "DOUT_2") (pintype "output"))
      (node (ref "D43") (pin "4") (pinfunction "DIN_4") (pintype "input"))
    )
    (net (code "48") (name "Net-(D43-DOUT)") (class "Default")
      (node (ref "D43") (pin "2") (pinfunction "DOUT_2") (pintype "output"))
      (node (ref "D44") (pin "4") (pinfunction "DIN_4") (pintype "input"))
    )
    (net (code "49") (name "Net-(D44-DOUT)") (class "Default")
      (node (ref "D44") (pin "2") (pinfunction "DOUT_2") (pintype "output"))
      (node (ref "D45") (pin "4") (pinfunction "DIN_4") (pintype "input"))
    )
    (net (code "50") (name "Net-(D45-DOUT)") (class "Default")
      (node (ref "D45") (pin "2") (pinfunction "DOUT_2") (pintype "output"))
      (node (ref "D46") (pin "4") (pinfunction "DIN_4") (pintype "input"))
    )
    (net (code "51") (name "Net-(D46-DOUT)") (class "Default")
      (node (ref "D46") (pin "2") (pinfunction "DOUT_2") (pintype "output"))
      (node (ref "D47") (pin "4") (pinfunction "DIN_4") (pintype "input"))
    )
    (net (code "52") (name "Net-(D47-DOUT)") (class "Default")
      (node (ref "D47") (pin "2") (pinfunction "DOUT_2") (pintype "output"))
      (node (ref "D48") (pin "4") (pinfunction "DIN_4") (pintype "input"))
    )
    (net (code "53") (name "Net-(D48-DOUT)") (class "Default")
      (node (ref "D48") (pin "2") (pinfunction "DOUT_2") (pintype "output"))
      (node (ref "D49") (pin "4") (pinfunction "DIN_4") (pintype "input"))
    )
    (net (code "54") (name "Net-(D49-DOUT)") (class "Default")
      (node (ref "D49") (pin "2") (pinfunction "DOUT_2") (pintype "output"))
      (node (ref "D50") (pin "4") (pinfunction "DIN_4") (pintype "input"))
    )
    (net (code "55") (name "Net-(D50-DOUT)") (class "Default")
      (node (ref "D50") (pin "2") (pinfunction "DOUT_2") (pintype "output"))
      (node (ref "D51") (pin "4") (pinfunction "DIN_4") (pintype "input"))
    )
    (net (code "56") (name "Net-(D51-DOUT)") (class "Default")
      (node (ref "D51") (pin "2") (pinfunction "DOUT_2") (pintype "output"))
      (node (ref "D52") (pin "4") (pinfunction "DIN_4") (pintype "input"))
    )
    (net (code "57") (name "Net-(D52-DOUT)") (class "Default")
      (node (ref "D52") (pin "2") (pinfunction "DOUT_2") (pintype "output"))
      (node (ref "D53") (pin "4") (pinfunction "DIN_4") (pintype "input"))
    )
    (net (code "58") (name "Net-(D53-DOUT)") (class "Default")
      (node (ref "D53") (pin "2") (pinfunction "DOUT_2") (pintype "output"))
      (node (ref "D54") (pin "4") (pinfunction "DIN_4") (pintype "input"))
    )
    (net (code "59") (name "Net-(D54-DOUT)") (class "Default")
      (node (ref "D54") (pin "2") (pinfunction "DOUT_2") (pintype "output"))
      (node (ref "D55") (pin "4") (pinfunction "DIN_4") (pintype "input"))
    )
    (net (code "60") (name "Net-(D55-DOUT)") (class "Default")
      (node (ref "D55") (pin "2") (pinfunction "DOUT_2") (pintype "output"))
      (node (ref "D56") (pin "4") (pinfunction "DIN_4") (pintype "input"))
    )
    (net (code "61") (name "Net-(D56-DOUT)") (class "Default")
      (node (ref "D56") (pin "2") (pinfunction "DOUT_2") (pintype "output"))
      (node (ref "D57") (pin "4") (pinfunction "DIN_4") (pintype "input"))
    )
    (net (code "62") (name "Net-(D57-DOUT)") (class "Default")
      (node (ref "D57") (pin "2") (pinfunction "DOUT_2") (pintype "output"))
      (node (ref "D58") (pin "4") (pinfunction "DIN_4") (pintype "input"))
    )
    (net (code "63") (name "Net-(D58-DOUT)") (class "Default")
      (node (ref "D58") (pin "2") (pinfunction "DOUT_2") (pintype "output"))
      (node (ref "D59") (pin "4") (pinfunction "DIN_4") (pintype "input"))
    )
    (net (code "64") (name "Net-(D59-DOUT)") (class "Default")
      (node (ref "D59") (pin "2") (pinfunction "DOUT_2") (pintype "output"))
      (node (ref "D60") (pin "4") (pinfunction "DIN_4") (pintype "input"))
    )
    (net (code "65") (name "Net-(D60-DOUT)") (class "Default")
      (node (ref "D60") (pin "2") (pinfunction "DOUT_2") (pintype "output"))
      (node (ref "D61") (pin "4") (pinfunction "DIN_4") (pintype "input"))
    )
    (net (code "66") (name "Net-(D61-DOUT)") (class "Default")
      (node (ref "D61") (pin "2") (pinfunction "DOUT_2") (pintype "output"))
      (node (ref "D62") (pin "4") (pinfunction "DIN_4") (pintype "input"))
    )
    (net (code "67") (name "Net-(D62-DOUT)") (class "Default")
      (node (ref "D62") (pin "2") (pinfunction "DOUT_2") (pintype "output"))
      (node (ref "D63") (pin "4") (pinfunction "DIN_4") (pintype "input"))
    )
    (net (code "68") (name "Net-(D63-DOUT)") (class "Default")
      (node (ref "D63") (pin "2") (pinfunction "DOUT_2") (pintype "output"))
      (node (ref "D64") (pin "4") (pinfunction "DIN_4") (pintype "input"))
    )
    (net (code "69") (name "Net-(D64-DOUT)") (class "Default")
      (node (ref "D64") (pin "2") (pinfunction "DOUT_2") (pintype "output"))
      (node (ref "D65") (pin "4") (pinfunction "DIN_4") (pintype "input"))
    )
    (net (code "70") (name "Net-(D65-DOUT)") (class "Default")
      (node (ref "D65") (pin "2") (pinfunction "DOUT_2") (pintype "output"))
      (node (ref "D66") (pin "4") (pinfunction "DIN_4") (pintype "input"))
    )
    (net (code "71") (name "Net-(D66-DOUT)") (class "Default")
      (node (ref "D66") (pin "2") (pinfunction "DOUT_2") (pintype "output"))
      (node (ref "D67") (pin "4") (pinfunction "DIN_4") (pintype "input"))
    )
    (net (code "72") (name "Net-(D67-DOUT)") (class "Default")
      (node (ref "D67") (pin "2") (pinfunction "DOUT_2") (pintype "output"))
      (node (ref "D68") (pin "4") (pinfunction "DIN_4") (pintype "input"))
    )
    (net (code "73") (name "Net-(D68-DOUT)") (class "Default")
      (node (ref "D68") (pin "2") (pinfunction "DOUT_2") (pintype "output"))
      (node (ref "D69") (pin "4") (pinfunction "DIN_4") (pintype "input"))
    )
    (net (code "74") (name "Net-(D69-DOUT)") (class "Default")
      (node (ref "D69") (pin "2") (pinfunction "DOUT_2") (pintype "output"))
      (node (ref "D70") (pin "4") (pinfunction "DIN_4") (pintype "input"))
    )
    (net (code "75") (name "Net-(D70-DOUT)") (class "Default")
      (node (ref "D70") (pin "2") (pinfunction "DOUT_2") (pintype "output"))
      (node (ref "D71") (pin "4") (pinfunction "DIN_4") (pintype "input"))
    )
    (net (code "76") (name "Net-(D71-DOUT)") (class "Default")
      (node (ref "D71") (pin "2") (pinfunction "DOUT_2") (pintype "output"))
      (node (ref "D72") (pin "4") (pinfunction "DIN_4") (pintype "input"))
    )
    (net (code "77") (name "Net-(D72-DOUT)") (class "Default")
      (node (ref "D72") (pin "2") (pinfunction "DOUT_2") (pintype "output"))
      (node (ref "D73") (pin "4") (pinfunction "DIN_4") (pintype "input"))
    )
    (net (code "78") (name "Net-(D73-DOUT)") (class "Default")
      (node (ref "D73") (pin "2") (pinfunction "DOUT_2") (pintype "output"))
      (node (ref "D74") (pin "4") (pinfunction "DIN_4") (pintype "input"))
    )
    (net (code "79") (name "Net-(D74-DOUT)") (class "Default")
      (node (ref "D74") (pin "2") (pinfunction "DOUT_2") (pintype "output"))
      (node (ref "D75") (pin "4") (pinfunction "DIN_4") (pintype "input"))
    )
    (net (code "80") (name "Net-(D75-DOUT)") (class "Default")
      (node (ref "D75") (pin "2") (pinfunction "DOUT_2") (pintype "output"))
      (node (ref "D76") (pin "4") (pinfunction "DIN_4") (pintype "input"))
    )
    (net (code "81") (name "Net-(D76-DOUT)") (class "Default")
      (node (ref "D76") (pin "2") (pinfunction "DOUT_2") (pintype "output"))
      (node (ref "D77") (pin "4") (pinfunction "DIN_4") (pintype "input"))
    )
    (net (code "82") (name "Net-(D77-DOUT)") (class "Default")
      (node (ref "D77") (pin "2") (pinfunction "DOUT_2") (pintype "output"))
      (node (ref "D78") (pin "4") (pinfunction "DIN_4") (pintype "input"))
    )
    (net (code "83") (name "Net-(D78-DOUT)") (class "Default")
      (node (ref "D78") (pin "2") (pinfunction "DOUT_2") (pintype "output"))
      (node (ref "D79") (pin "4") (pinfunction "DIN_4") (pintype "input"))
    )
    (net (code "84") (name "Net-(D79-DOUT)") (class "Default")
      (node (ref "D79") (pin "2") (pinfunction "DOUT_2") (pintype "output"))
      (node (ref "D80") (pin "4") (pinfunction "DIN_4") (pintype "input"))
    )
    (net (code "85") (name "Net-(D80-DOUT)") (class "Default")
      (node (ref "D80") (pin "2") (pinfunction "DOUT_2") (pintype "output"))
      (node (ref "D81") (pin "4") (pinfunction "DIN_4") (pintype "input"))
    )
    (net (code "86") (name "Net-(D81-DOUT)") (class "Default")
      (node (ref "D81") (pin "2") (pinfunction "DOUT_2") (pintype "output"))
      (node (ref "D82") (pin "4") (pinfunction "DIN_4") (pintype "input"))
    )
    (net (code "87") (name "Net-(D82-DOUT)") (class "Default")
      (node (ref "D82") (pin "2") (pinfunction "DOUT_2") (pintype "output"))
      (node (ref "D83") (pin "4") (pinfunction "DIN_4") (pintype "input"))
    )
    (net (code "88") (name "Net-(D83-DOUT)") (class "Default")
      (node (ref "D83") (pin "2") (pinfunction "DOUT_2") (pintype "output"))
      (node (ref "D84") (pin "4") (pinfunction "DIN_4") (pintype "input"))
    )
    (net (code "89") (name "Net-(D84-DOUT)") (class "Default")
      (node (ref "D84") (pin "2") (pinfunction "DOUT_2") (pintype "output"))
      (node (ref "D85") (pin "4") (pinfunction "DIN_4") (pintype "input"))
    )
    (net (code "90") (name "Net-(D86-DOUT)") (class "Default")
      (node (ref "D86") (pin "2") (pinfunction "DOUT_2") (pintype "output"))
      (node (ref "D87") (pin "4") (pinfunction "DIN_4") (pintype "input"))
    )
    (net (code "91") (name "Net-(D87-DOUT)") (class "Default")
      (node (ref "D87") (pin "2") (pinfunction "DOUT_2") (pintype "output"))
      (node (ref "D88") (pin "4") (pinfunction "DIN_4") (pintype "input"))
    )
    (net (code "92") (name "Net-(D88-DOUT)") (class "Default")
      (node (ref "D88") (pin "2") (pinfunction "DOUT_2") (pintype "output"))
      (node (ref "D89") (pin "4") (pinfunction "DIN_4") (pintype "input"))
    )
    (net (code "93") (name "Net-(D89-DOUT)") (class "Default")
      (node (ref "D89") (pin "2") (pinfunction "DOUT_2") (pintype "output"))
      (node (ref "D90") (pin "4") (pinfunction "DIN_4") (pintype "input"))
    )
    (net (code "94") (name "Net-(D90-DOUT)") (class "Default")
      (node (ref "D90") (pin "2") (pinfunction "DOUT_2") (pintype "output"))
      (node (ref "D91") (pin "4") (pinfunction "DIN_4") (pintype "input"))
    )
    (net (code "95") (name "Net-(D91-DOUT)") (class "Default")
      (node (ref "D91") (pin "2") (pinfunction "DOUT_2") (pintype "output"))
      (node (ref "D92") (pin "4") (pinfunction "DIN_4") (pintype "input"))
    )
    (net (code "96") (name "Net-(D92-DOUT)") (class "Default")
      (node (ref "D92") (pin "2") (pinfunction "DOUT_2") (pintype "output"))
      (node (ref "D93") (pin "4") (pinfunction "DIN_4") (pintype "input"))
    )
    (net (code "97") (name "Net-(D93-DOUT)") (class "Default")
      (node (ref "D93") (pin "2") (pinfunction "DOUT_2") (pintype "output"))
      (node (ref "D94") (pin "4") (pinfunction "DIN_4") (pintype "input"))
    )
    (net (code "98") (name "Net-(D94-DOUT)") (class "Default")
      (node (ref "D94") (pin "2") (pinfunction "DOUT_2") (pintype "output"))
      (node (ref "D95") (pin "4") (pinfunction "DIN_4") (pintype "input"))
    )
    (net (code "99") (name "Net-(D95-DOUT)") (class "Default")
      (node (ref "D95") (pin "2") (pinfunction "DOUT_2") (pintype "output"))
      (node (ref "D96") (pin "4") (pinfunction "DIN_4") (pintype "input"))
    )
    (net (code "100") (name "Net-(D96-DOUT)") (class "Default")
      (node (ref "D96") (pin "2") (pinfunction "DOUT_2") (pintype "output"))
      (node (ref "D97") (pin "4") (pinfunction "DIN_4") (pintype "input"))
    )
    (net (code "101") (name "Net-(D97-DOUT)") (class "Default")
      (node (ref "D97") (pin "2") (pinfunction "DOUT_2") (pintype "output"))
      (node (ref "D98") (pin "4") (pinfunction "DIN_4") (pintype "input"))
    )
    (net (code "102") (name "Net-(D98-DOUT)") (class "Default")
      (node (ref "D98") (pin "2") (pinfunction "DOUT_2") (pintype "output"))
      (node (ref "D99") (pin "4") (pinfunction "DIN_4") (pintype "input"))
    )
    (net (code "103") (name "Net-(D100-DIN)") (class "Default")
      (node (ref "D100") (pin "4") (pinfunction "DIN_4") (pintype "input"))
      (node (ref "D99") (pin "2") (pinfunction "DOUT_2") (pintype "output"))
    )
    (net (code "104") (name "Net-(D100-DOUT)") (class "Default")
      (node (ref "D100") (pin "2") (pinfunction "DOUT_2") (pintype "output"))
      (node (ref "D101") (pin "4") (pinfunction "DIN_4") (pintype "input"))
    )
    (net (code "105") (name "Net-(D101-DOUT)") (class "Default")
      (node (ref "D101") (pin "2") (pinfunction "DOUT_2") (pintype "output"))
      (node (ref "D102") (pin "4") (pinfunction "DIN_4") (pintype "input"))
    )
    (net (code "106") (name "Net-(D102-DOUT)") (class "Default")
      (node (ref "D102") (pin "2") (pinfunction "DOUT_2") (pintype "output"))
      (node (ref "D103") (pin "4") (pinfunction "DIN_4") (pintype "input"))
    )
    (net (code "107") (name "Net-(D103-DOUT)") (class "Default")
      (node (ref "D103") (pin "2") (pinfunction "DOUT_2") (pintype "output"))
      (node (ref "D104") (pin "4") (pinfunction "DIN_4") (pintype "input"))
    )
    (net (code "108") (name "Net-(D104-DOUT)") (class "Default")
      (node (ref "D104") (pin "2") (pinfunction "DOUT_2") (pintype "output"))
      (node (ref "D105") (pin "4") (pinfunction "DIN_4") (pintype "input"))
    )
    (net (code "109") (name "Net-(D105-DOUT)") (class "Default")
      (node (ref "D105") (pin "2") (pinfunction "DOUT_2") (pintype "output"))
      (node (ref "D106") (pin "4") (pinfunction "DIN_4") (pintype "input"))
    )
    (net (code "110") (name "Net-(D106-DOUT)") (class "Default")
      (node (ref "D106") (pin "2") (pinfunction "DOUT_2") (pintype "output"))
      (node (ref "D107") (pin "4") (pinfunction "DIN_4") (pintype "input"))
    )
    (net (code "111") (name "Net-(D107-DOUT)") (class "Default")
      (node (ref "D107") (pin "2") (pinfunction "DOUT_2") (pintype "output"))
      (node (ref "D108") (pin "4") (pinfunction "DIN_4") (pintype "input"))
    )
    (net (code "112") (name "Net-(LED1-Pad1)") (class "Default")
      (node (ref "LED1") (pin "1") (pinfunction "1_1") (pintype "passive"))
      (node (ref "R1") (pin "1") (pinfunction "1_1") (pintype "passive"))
    )
    (net (code "113") (name "unconnected-(D85-DOUT-Pad2)") (class "Default")
      (node (ref "D85") (pin "2") (pinfunction "DOUT_2") (pintype "output"))
    )
    (net (code "114") (name "unconnected-(D108-DOUT-Pad2)") (class "Default")
      (node (ref "D108") (pin "2") (pinfunction "DOUT_2") (pintype "output"))
    )
  )
)
